# ELC0102_-_Switch_Interface.net
KiCad netlist of a schematic drawn in Altium Designer
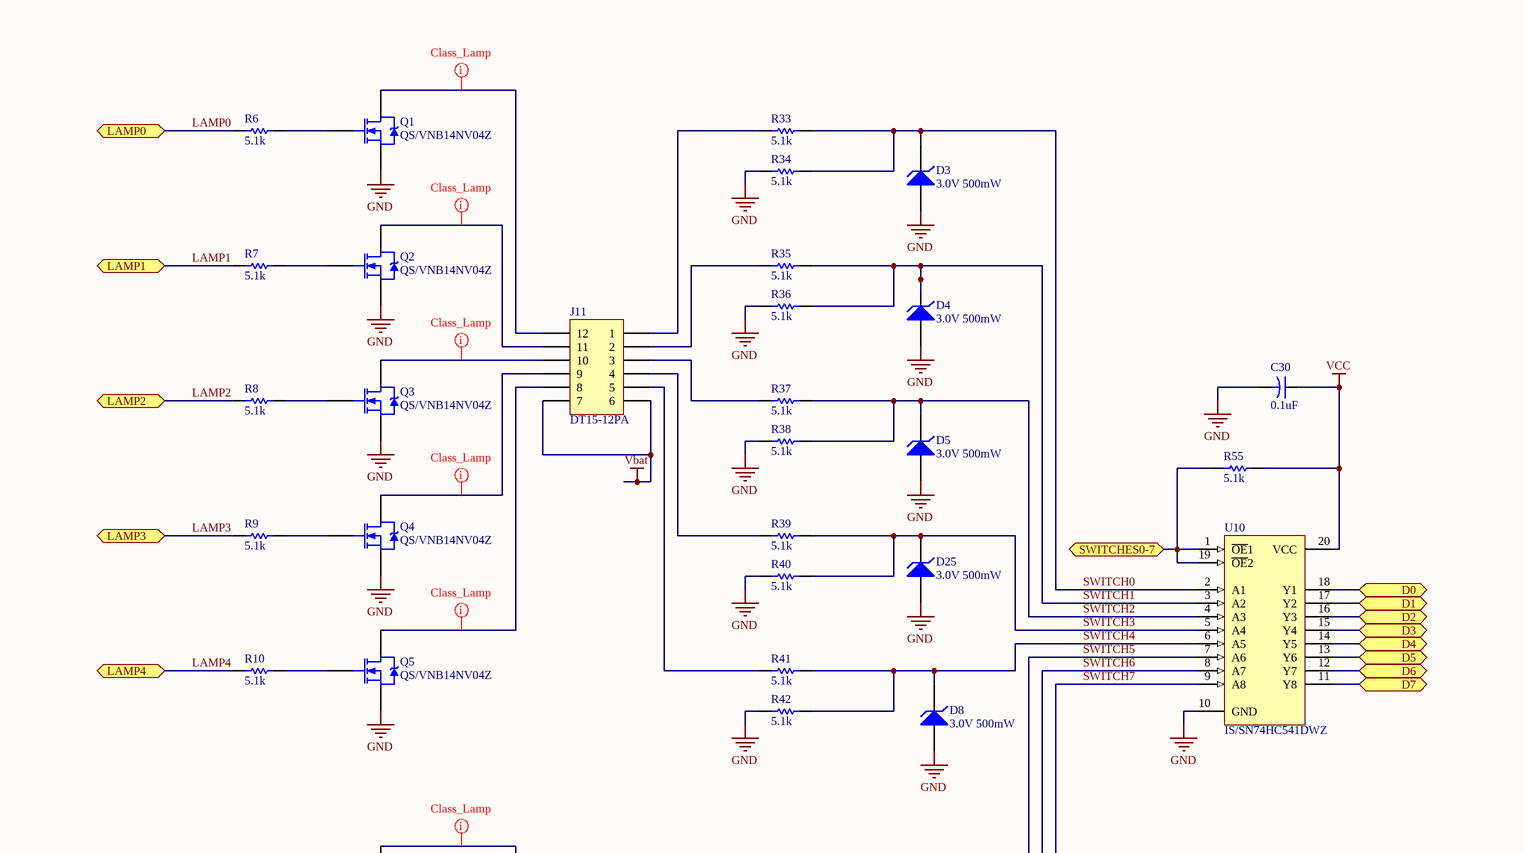
[diagram p0: ELC0102 - Switch Interface.SchDoc, top left]
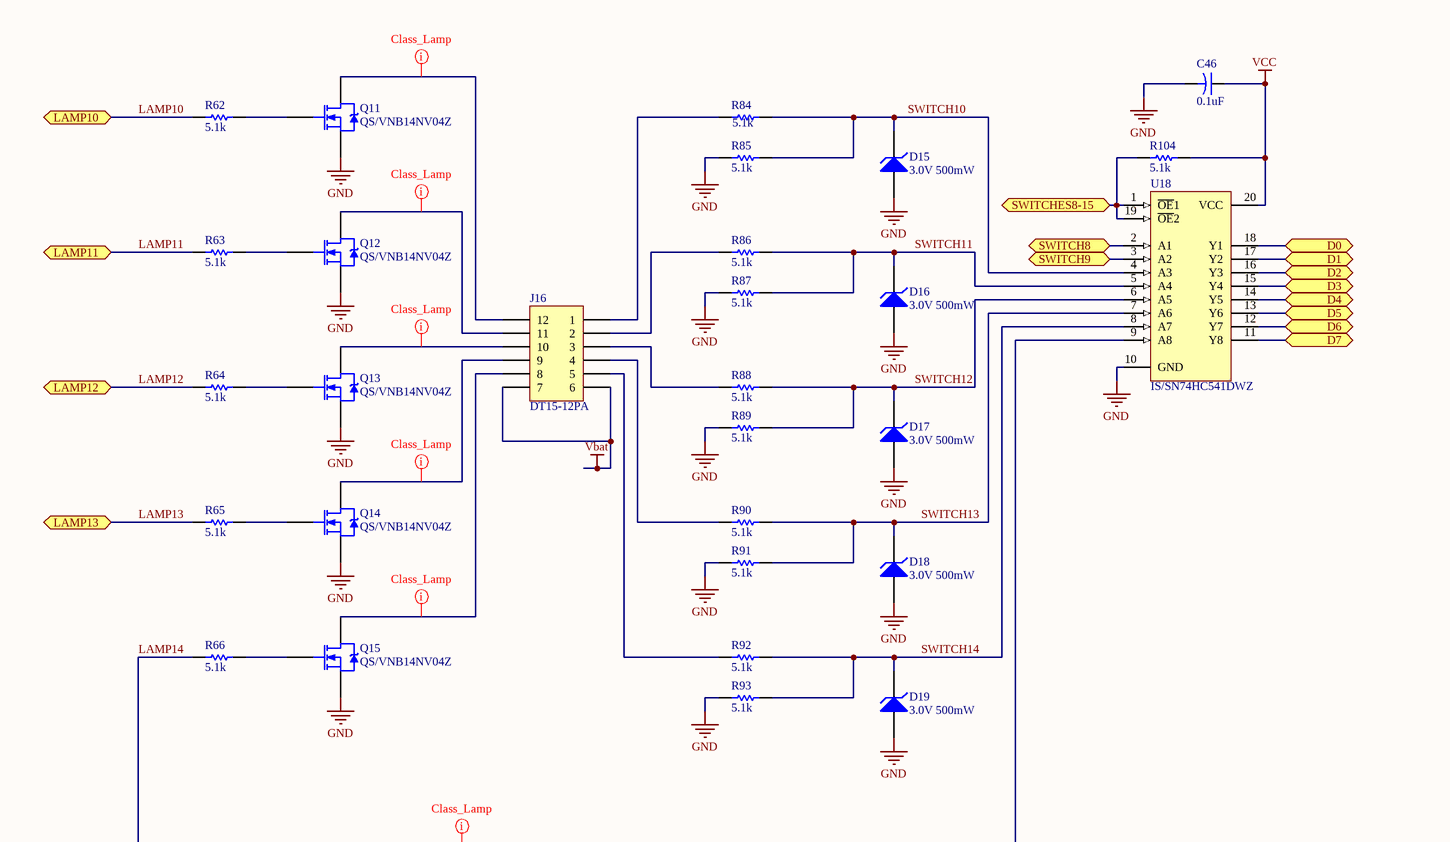
[diagram p1: ELC0102 - Switch Interface.SchDoc, top right]
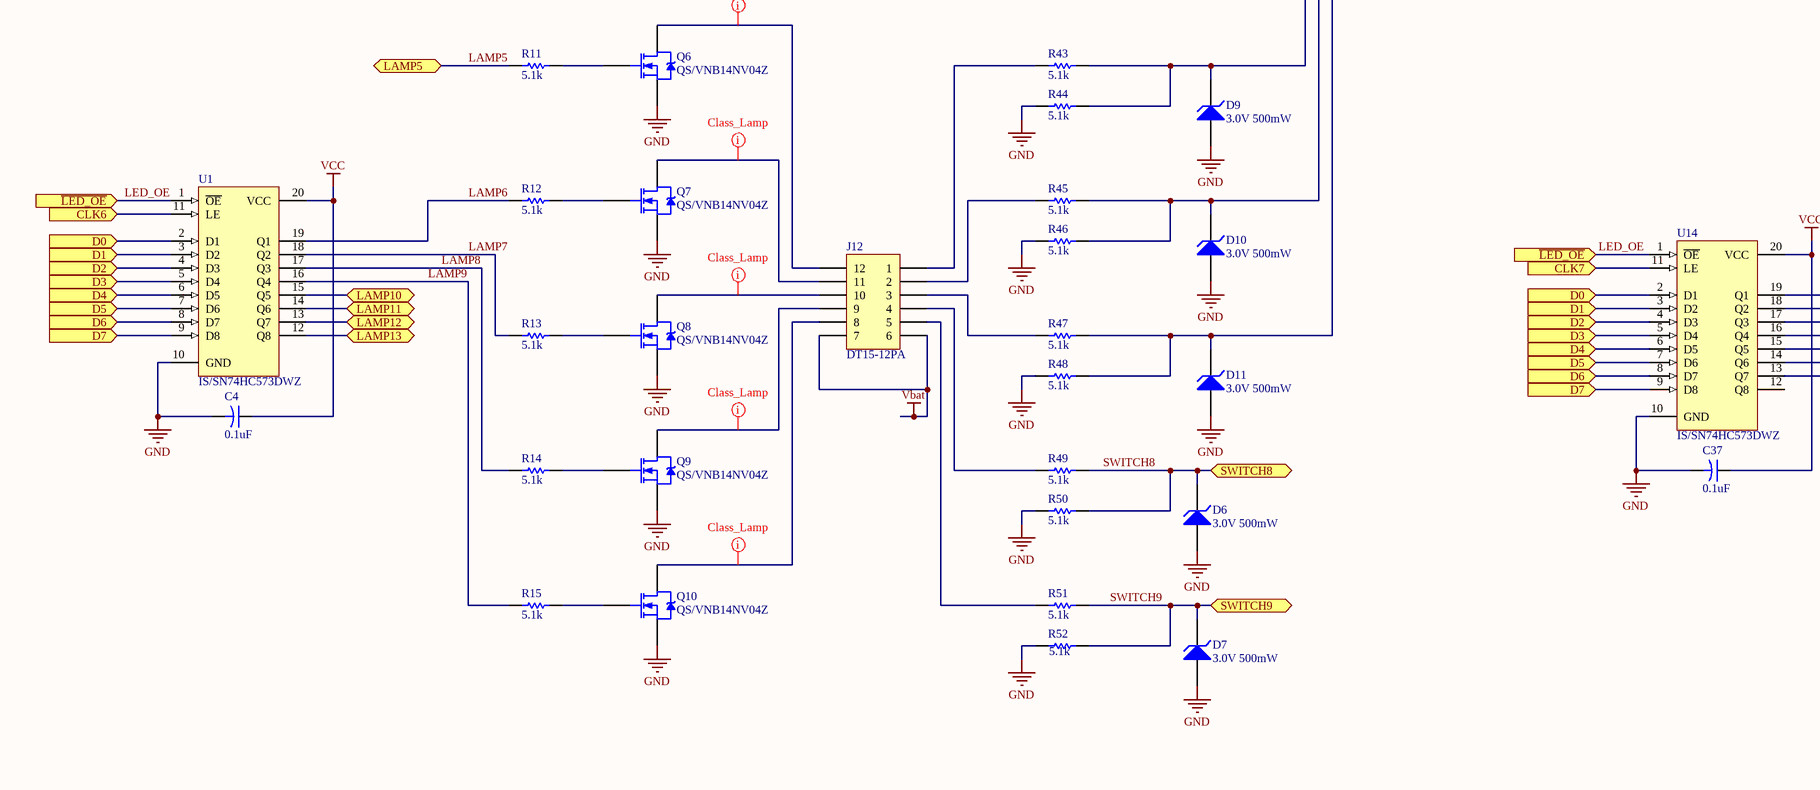
[diagram p2: ELC0102 - Switch Interface.SchDoc, bottom left]
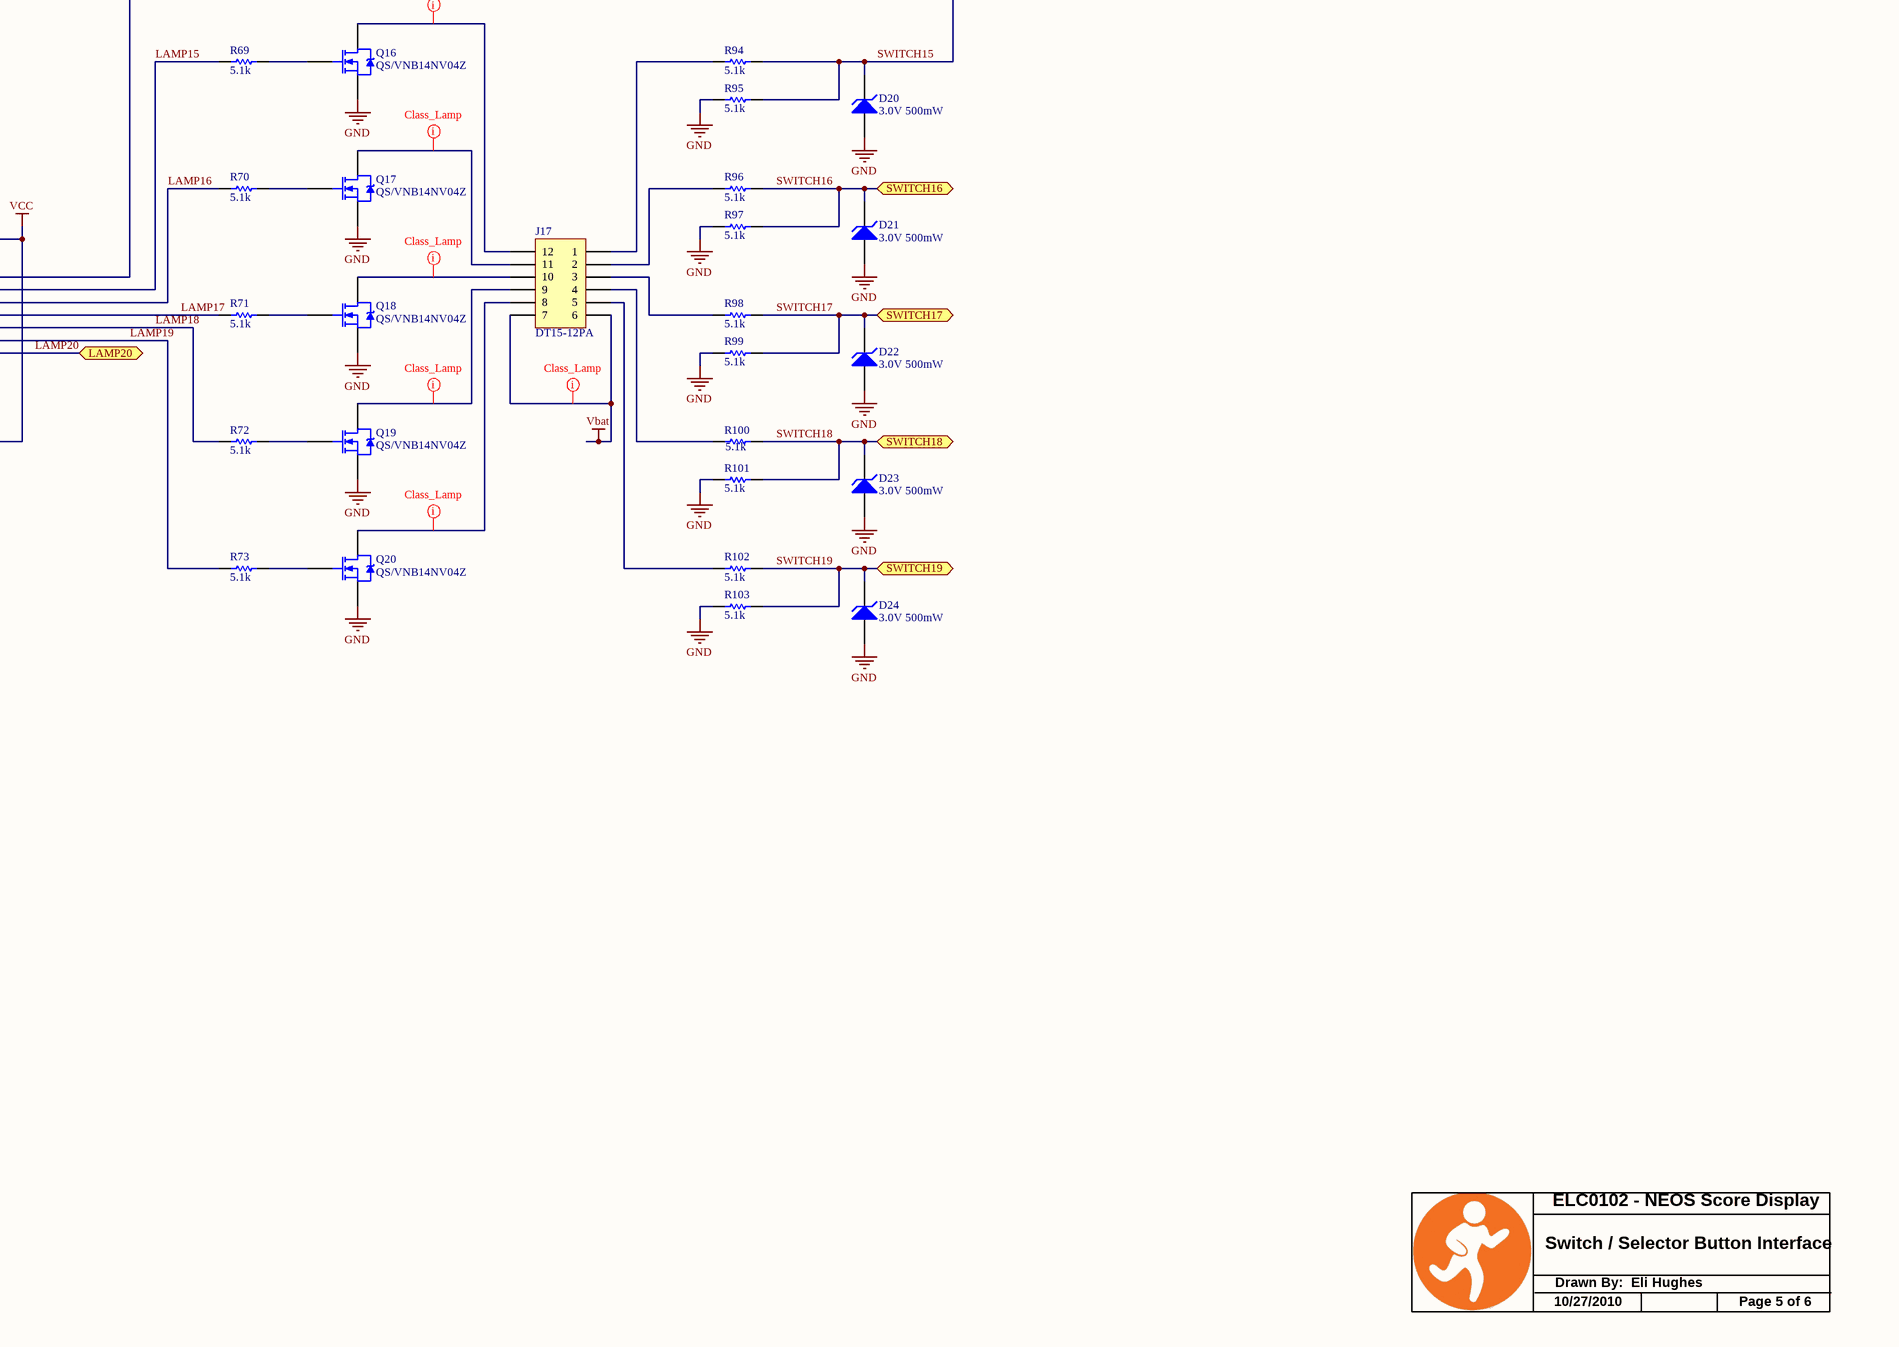
[diagram p3: ELC0102 - Switch Interface.SchDoc, bottom right]

(export (version "E")
  (design (tool "Eeschema 10.0.6"))
  (components
    (comp (ref "C4")
      (value "0.1uF")
      (footprint "C0805")
      (description "CAP .10UF 50V CERAMIC X7R 0805")
      (fields
        (field (name "MANUFACTURER") "Kemet")
        (field (name "MANUFACTURER PART NUMBER") "C0805C104K5RACTU")
        (field (name "SOURCE") "Digikey")
      )
      (libsource (lib "ELC102 - Scoreboard") (part "CS/C0805C104K5RACK"))
    )
    (comp (ref "C30")
      (value "0.1uF")
      (footprint "C0805")
      (description "CAP .10UF 50V CERAMIC X7R 0805")
      (fields
        (field (name "MANUFACTURER") "Kemet")
        (field (name "MANUFACTURER PART NUMBER") "C0805C104K5RACTU")
        (field (name "SOURCE") "Digikey")
      )
      (libsource (lib "ELC102 - Scoreboard") (part "CS/C0805C104K5RACK"))
    )
    (comp (ref "C37")
      (value "0.1uF")
      (footprint "C0805")
      (description "CAP .10UF 50V CERAMIC X7R 0805")
      (fields
        (field (name "MANUFACTURER") "Kemet")
        (field (name "MANUFACTURER PART NUMBER") "C0805C104K5RACTU")
        (field (name "SOURCE") "Digikey")
      )
      (libsource (lib "ELC102 - Scoreboard") (part "CS/C0805C104K5RACK"))
    )
    (comp (ref "C46")
      (value "0.1uF")
      (footprint "C0805")
      (description "CAP .10UF 50V CERAMIC X7R 0805")
      (fields
        (field (name "MANUFACTURER") "Kemet")
        (field (name "MANUFACTURER PART NUMBER") "C0805C104K5RACTU")
        (field (name "SOURCE") "Digikey")
      )
      (libsource (lib "ELC102 - Scoreboard") (part "CS/C0805C104K5RACK"))
    )
    (comp (ref "D3")
      (value "3.0V 500mW")
      (footprint "SOD123")
      (description "Zener 3.0V SOD-123")
      (fields
        (field (name "MANUFACTURER") "ON Semiconductor")
        (field (name "MANUFACTURER PART NUMBER") "MMSZ5225BT1G")
        (field (name "SOURCE") "Digikey")
      )
      (libsource (lib "ScoreBoard") (part "DS/MMSZ5225BT1Z"))
    )
    (comp (ref "D4")
      (value "3.0V 500mW")
      (footprint "SOD123")
      (description "Zener 3.0V SOD-123")
      (fields
        (field (name "MANUFACTURER") "ON Semiconductor")
        (field (name "MANUFACTURER PART NUMBER") "MMSZ5225BT1G")
        (field (name "SOURCE") "Digikey")
      )
      (libsource (lib "ScoreBoard") (part "DS/MMSZ5225BT1Z"))
    )
    (comp (ref "D5")
      (value "3.0V 500mW")
      (footprint "SOD123")
      (description "Zener 3.0V SOD-123")
      (fields
        (field (name "MANUFACTURER") "ON Semiconductor")
        (field (name "MANUFACTURER PART NUMBER") "MMSZ5225BT1G")
        (field (name "SOURCE") "Digikey")
      )
      (libsource (lib "ScoreBoard") (part "DS/MMSZ5225BT1Z"))
    )
    (comp (ref "D6")
      (value "3.0V 500mW")
      (footprint "SOD123")
      (description "Zener 3.0V SOD-123")
      (fields
        (field (name "MANUFACTURER") "ON Semiconductor")
        (field (name "MANUFACTURER PART NUMBER") "MMSZ5225BT1G")
        (field (name "SOURCE") "Digikey")
      )
      (libsource (lib "ScoreBoard") (part "DS/MMSZ5225BT1Z"))
    )
    (comp (ref "D7")
      (value "3.0V 500mW")
      (footprint "SOD123")
      (description "Zener 3.0V SOD-123")
      (fields
        (field (name "MANUFACTURER") "ON Semiconductor")
        (field (name "MANUFACTURER PART NUMBER") "MMSZ5225BT1G")
        (field (name "SOURCE") "Digikey")
      )
      (libsource (lib "ScoreBoard") (part "DS/MMSZ5225BT1Z"))
    )
    (comp (ref "D8")
      (value "3.0V 500mW")
      (footprint "SOD123")
      (description "Zener 3.0V SOD-123")
      (fields
        (field (name "MANUFACTURER") "ON Semiconductor")
        (field (name "MANUFACTURER PART NUMBER") "MMSZ5225BT1G")
        (field (name "SOURCE") "Digikey")
      )
      (libsource (lib "ScoreBoard") (part "DS/MMSZ5225BT1Z"))
    )
    (comp (ref "D9")
      (value "3.0V 500mW")
      (footprint "SOD123")
      (description "Zener 3.0V SOD-123")
      (fields
        (field (name "MANUFACTURER") "ON Semiconductor")
        (field (name "MANUFACTURER PART NUMBER") "MMSZ5225BT1G")
        (field (name "SOURCE") "Digikey")
      )
      (libsource (lib "ScoreBoard") (part "DS/MMSZ5225BT1Z"))
    )
    (comp (ref "D10")
      (value "3.0V 500mW")
      (footprint "SOD123")
      (description "Zener 3.0V SOD-123")
      (fields
        (field (name "MANUFACTURER") "ON Semiconductor")
        (field (name "MANUFACTURER PART NUMBER") "MMSZ5225BT1G")
        (field (name "SOURCE") "Digikey")
      )
      (libsource (lib "ScoreBoard") (part "DS/MMSZ5225BT1Z"))
    )
    (comp (ref "D11")
      (value "3.0V 500mW")
      (footprint "SOD123")
      (description "Zener 3.0V SOD-123")
      (fields
        (field (name "MANUFACTURER") "ON Semiconductor")
        (field (name "MANUFACTURER PART NUMBER") "MMSZ5225BT1G")
        (field (name "SOURCE") "Digikey")
      )
      (libsource (lib "ScoreBoard") (part "DS/MMSZ5225BT1Z"))
    )
    (comp (ref "D15")
      (value "3.0V 500mW")
      (footprint "SOD123")
      (description "Zener 3.0V SOD-123")
      (fields
        (field (name "MANUFACTURER") "ON Semiconductor")
        (field (name "MANUFACTURER PART NUMBER") "MMSZ5225BT1G")
        (field (name "SOURCE") "Digikey")
      )
      (libsource (lib "ScoreBoard") (part "DS/MMSZ5225BT1Z"))
    )
    (comp (ref "D16")
      (value "3.0V 500mW")
      (footprint "SOD123")
      (description "Zener 3.0V SOD-123")
      (fields
        (field (name "MANUFACTURER") "ON Semiconductor")
        (field (name "MANUFACTURER PART NUMBER") "MMSZ5225BT1G")
        (field (name "SOURCE") "Digikey")
      )
      (libsource (lib "ScoreBoard") (part "DS/MMSZ5225BT1Z"))
    )
    (comp (ref "D17")
      (value "3.0V 500mW")
      (footprint "SOD123")
      (description "Zener 3.0V SOD-123")
      (fields
        (field (name "MANUFACTURER") "ON Semiconductor")
        (field (name "MANUFACTURER PART NUMBER") "MMSZ5225BT1G")
        (field (name "SOURCE") "Digikey")
      )
      (libsource (lib "ScoreBoard") (part "DS/MMSZ5225BT1Z"))
    )
    (comp (ref "D18")
      (value "3.0V 500mW")
      (footprint "SOD123")
      (description "Zener 3.0V SOD-123")
      (fields
        (field (name "MANUFACTURER") "ON Semiconductor")
        (field (name "MANUFACTURER PART NUMBER") "MMSZ5225BT1G")
        (field (name "SOURCE") "Digikey")
      )
      (libsource (lib "ScoreBoard") (part "DS/MMSZ5225BT1Z"))
    )
    (comp (ref "D19")
      (value "3.0V 500mW")
      (footprint "SOD123")
      (description "Zener 3.0V SOD-123")
      (fields
        (field (name "MANUFACTURER") "ON Semiconductor")
        (field (name "MANUFACTURER PART NUMBER") "MMSZ5225BT1G")
        (field (name "SOURCE") "Digikey")
      )
      (libsource (lib "ScoreBoard") (part "DS/MMSZ5225BT1Z"))
    )
    (comp (ref "D20")
      (value "3.0V 500mW")
      (footprint "SOD123")
      (description "Zener 3.0V SOD-123")
      (fields
        (field (name "MANUFACTURER") "ON Semiconductor")
        (field (name "MANUFACTURER PART NUMBER") "MMSZ5225BT1G")
        (field (name "SOURCE") "Digikey")
      )
      (libsource (lib "ScoreBoard") (part "DS/MMSZ5225BT1Z"))
    )
    (comp (ref "D21")
      (value "3.0V 500mW")
      (footprint "SOD123")
      (description "Zener 3.0V SOD-123")
      (fields
        (field (name "MANUFACTURER") "ON Semiconductor")
        (field (name "MANUFACTURER PART NUMBER") "MMSZ5225BT1G")
        (field (name "SOURCE") "Digikey")
      )
      (libsource (lib "ScoreBoard") (part "DS/MMSZ5225BT1Z"))
    )
    (comp (ref "D22")
      (value "3.0V 500mW")
      (footprint "SOD123")
      (description "Zener 3.0V SOD-123")
      (fields
        (field (name "MANUFACTURER") "ON Semiconductor")
        (field (name "MANUFACTURER PART NUMBER") "MMSZ5225BT1G")
        (field (name "SOURCE") "Digikey")
      )
      (libsource (lib "ScoreBoard") (part "DS/MMSZ5225BT1Z"))
    )
    (comp (ref "D23")
      (value "3.0V 500mW")
      (footprint "SOD123")
      (description "Zener 3.0V SOD-123")
      (fields
        (field (name "MANUFACTURER") "ON Semiconductor")
        (field (name "MANUFACTURER PART NUMBER") "MMSZ5225BT1G")
        (field (name "SOURCE") "Digikey")
      )
      (libsource (lib "ScoreBoard") (part "DS/MMSZ5225BT1Z"))
    )
    (comp (ref "D24")
      (value "3.0V 500mW")
      (footprint "SOD123")
      (description "Zener 3.0V SOD-123")
      (fields
        (field (name "MANUFACTURER") "ON Semiconductor")
        (field (name "MANUFACTURER PART NUMBER") "MMSZ5225BT1G")
        (field (name "SOURCE") "Digikey")
      )
      (libsource (lib "ScoreBoard") (part "DS/MMSZ5225BT1Z"))
    )
    (comp (ref "D25")
      (value "3.0V 500mW")
      (footprint "SOD123")
      (description "Zener 3.0V SOD-123")
      (fields
        (field (name "MANUFACTURER") "ON Semiconductor")
        (field (name "MANUFACTURER PART NUMBER") "MMSZ5225BT1G")
        (field (name "SOURCE") "Digikey")
      )
      (libsource (lib "ScoreBoard") (part "DS/MMSZ5225BT1Z"))
    )
    (comp (ref "J11")
      (value "DT15-12PA")
      (footprint "JDT1512PA00Z")
      (description "Deutsch 12P Sealed PCB connector")
      (fields (field (name "MANUFACTURER") "Deutsch"))
      (libsource (lib "ScoreBoard") (part "JDT1512PA00Z"))
    )
    (comp (ref "J12")
      (value "DT15-12PA")
      (footprint "JDT1512PA00Z")
      (description "Deutsch 12P Sealed PCB connector")
      (fields (field (name "MANUFACTURER") "Deutsch"))
      (libsource (lib "ScoreBoard") (part "JDT1512PA00Z"))
    )
    (comp (ref "J16")
      (value "DT15-12PA")
      (footprint "JDT1512PA00Z")
      (description "Deutsch 12P Sealed PCB connector")
      (fields (field (name "MANUFACTURER") "Deutsch"))
      (libsource (lib "ScoreBoard") (part "JDT1512PA00Z"))
    )
    (comp (ref "J17")
      (value "DT15-12PA")
      (footprint "JDT1512PA00Z")
      (description "Deutsch 12P Sealed PCB connector")
      (fields (field (name "MANUFACTURER") "Deutsch"))
      (libsource (lib "ScoreBoard") (part "JDT1512PA00Z"))
    )
    (comp (ref "Q1")
      (value "QS/VNB14NV04Z")
      (footprint "D2PAK")
      (description "HEXFET Power MOSFET")
      (fields
        (field (name "MANUFACTURER") "STMicroelectronics")
        (field (name "MANUFACTURER PART NUMBER") "VNB14NV04")
        (field (name "SOURCE") "Digikey")
      )
      (libsource (lib "ScoreBoard") (part "QS/VNB14NV04Z"))
    )
    (comp (ref "Q2")
      (value "QS/VNB14NV04Z")
      (footprint "D2PAK")
      (description "HEXFET Power MOSFET")
      (fields
        (field (name "MANUFACTURER") "STMicroelectronics")
        (field (name "MANUFACTURER PART NUMBER") "VNB14NV04")
        (field (name "SOURCE") "Digikey")
      )
      (libsource (lib "ScoreBoard") (part "QS/VNB14NV04Z"))
    )
    (comp (ref "Q3")
      (value "QS/VNB14NV04Z")
      (footprint "D2PAK")
      (description "HEXFET Power MOSFET")
      (fields
        (field (name "MANUFACTURER") "STMicroelectronics")
        (field (name "MANUFACTURER PART NUMBER") "VNB14NV04")
        (field (name "SOURCE") "Digikey")
      )
      (libsource (lib "ScoreBoard") (part "QS/VNB14NV04Z"))
    )
    (comp (ref "Q4")
      (value "QS/VNB14NV04Z")
      (footprint "D2PAK")
      (description "HEXFET Power MOSFET")
      (fields
        (field (name "MANUFACTURER") "STMicroelectronics")
        (field (name "MANUFACTURER PART NUMBER") "VNB14NV04")
        (field (name "SOURCE") "Digikey")
      )
      (libsource (lib "ScoreBoard") (part "QS/VNB14NV04Z"))
    )
    (comp (ref "Q5")
      (value "QS/VNB14NV04Z")
      (footprint "D2PAK")
      (description "HEXFET Power MOSFET")
      (fields
        (field (name "MANUFACTURER") "STMicroelectronics")
        (field (name "MANUFACTURER PART NUMBER") "VNB14NV04")
        (field (name "SOURCE") "Digikey")
      )
      (libsource (lib "ScoreBoard") (part "QS/VNB14NV04Z"))
    )
    (comp (ref "Q6")
      (value "QS/VNB14NV04Z")
      (footprint "D2PAK")
      (description "HEXFET Power MOSFET")
      (fields
        (field (name "MANUFACTURER") "STMicroelectronics")
        (field (name "MANUFACTURER PART NUMBER") "VNB14NV04")
        (field (name "SOURCE") "Digikey")
      )
      (libsource (lib "ScoreBoard") (part "QS/VNB14NV04Z"))
    )
    (comp (ref "Q7")
      (value "QS/VNB14NV04Z")
      (footprint "D2PAK")
      (description "HEXFET Power MOSFET")
      (fields
        (field (name "MANUFACTURER") "STMicroelectronics")
        (field (name "MANUFACTURER PART NUMBER") "VNB14NV04")
        (field (name "SOURCE") "Digikey")
      )
      (libsource (lib "ScoreBoard") (part "QS/VNB14NV04Z"))
    )
    (comp (ref "Q8")
      (value "QS/VNB14NV04Z")
      (footprint "D2PAK")
      (description "HEXFET Power MOSFET")
      (fields
        (field (name "MANUFACTURER") "STMicroelectronics")
        (field (name "MANUFACTURER PART NUMBER") "VNB14NV04")
        (field (name "SOURCE") "Digikey")
      )
      (libsource (lib "ScoreBoard") (part "QS/VNB14NV04Z"))
    )
    (comp (ref "Q9")
      (value "QS/VNB14NV04Z")
      (footprint "D2PAK")
      (description "HEXFET Power MOSFET")
      (fields
        (field (name "MANUFACTURER") "STMicroelectronics")
        (field (name "MANUFACTURER PART NUMBER") "VNB14NV04")
        (field (name "SOURCE") "Digikey")
      )
      (libsource (lib "ScoreBoard") (part "QS/VNB14NV04Z"))
    )
    (comp (ref "Q10")
      (value "QS/VNB14NV04Z")
      (footprint "D2PAK")
      (description "HEXFET Power MOSFET")
      (fields
        (field (name "MANUFACTURER") "STMicroelectronics")
        (field (name "MANUFACTURER PART NUMBER") "VNB14NV04")
        (field (name "SOURCE") "Digikey")
      )
      (libsource (lib "ScoreBoard") (part "QS/VNB14NV04Z"))
    )
    (comp (ref "Q11")
      (value "QS/VNB14NV04Z")
      (footprint "D2PAK")
      (description "HEXFET Power MOSFET")
      (fields
        (field (name "MANUFACTURER") "STMicroelectronics")
        (field (name "MANUFACTURER PART NUMBER") "VNB14NV04")
        (field (name "SOURCE") "Digikey")
      )
      (libsource (lib "ScoreBoard") (part "QS/VNB14NV04Z"))
    )
    (comp (ref "Q12")
      (value "QS/VNB14NV04Z")
      (footprint "D2PAK")
      (description "HEXFET Power MOSFET")
      (fields
        (field (name "MANUFACTURER") "STMicroelectronics")
        (field (name "MANUFACTURER PART NUMBER") "VNB14NV04")
        (field (name "SOURCE") "Digikey")
      )
      (libsource (lib "ScoreBoard") (part "QS/VNB14NV04Z"))
    )
    (comp (ref "Q13")
      (value "QS/VNB14NV04Z")
      (footprint "D2PAK")
      (description "HEXFET Power MOSFET")
      (fields
        (field (name "MANUFACTURER") "STMicroelectronics")
        (field (name "MANUFACTURER PART NUMBER") "VNB14NV04")
        (field (name "SOURCE") "Digikey")
      )
      (libsource (lib "ScoreBoard") (part "QS/VNB14NV04Z"))
    )
    (comp (ref "Q14")
      (value "QS/VNB14NV04Z")
      (footprint "D2PAK")
      (description "HEXFET Power MOSFET")
      (fields
        (field (name "MANUFACTURER") "STMicroelectronics")
        (field (name "MANUFACTURER PART NUMBER") "VNB14NV04")
        (field (name "SOURCE") "Digikey")
      )
      (libsource (lib "ScoreBoard") (part "QS/VNB14NV04Z"))
    )
    (comp (ref "Q15")
      (value "QS/VNB14NV04Z")
      (footprint "D2PAK")
      (description "HEXFET Power MOSFET")
      (fields
        (field (name "MANUFACTURER") "STMicroelectronics")
        (field (name "MANUFACTURER PART NUMBER") "VNB14NV04")
        (field (name "SOURCE") "Digikey")
      )
      (libsource (lib "ScoreBoard") (part "QS/VNB14NV04Z"))
    )
    (comp (ref "Q16")
      (value "QS/VNB14NV04Z")
      (footprint "D2PAK")
      (description "HEXFET Power MOSFET")
      (fields
        (field (name "MANUFACTURER") "STMicroelectronics")
        (field (name "MANUFACTURER PART NUMBER") "VNB14NV04")
        (field (name "SOURCE") "Digikey")
      )
      (libsource (lib "ScoreBoard") (part "QS/VNB14NV04Z"))
    )
    (comp (ref "Q17")
      (value "QS/VNB14NV04Z")
      (footprint "D2PAK")
      (description "HEXFET Power MOSFET")
      (fields
        (field (name "MANUFACTURER") "STMicroelectronics")
        (field (name "MANUFACTURER PART NUMBER") "VNB14NV04")
        (field (name "SOURCE") "Digikey")
      )
      (libsource (lib "ScoreBoard") (part "QS/VNB14NV04Z"))
    )
    (comp (ref "Q18")
      (value "QS/VNB14NV04Z")
      (footprint "D2PAK")
      (description "HEXFET Power MOSFET")
      (fields
        (field (name "MANUFACTURER") "STMicroelectronics")
        (field (name "MANUFACTURER PART NUMBER") "VNB14NV04")
        (field (name "SOURCE") "Digikey")
      )
      (libsource (lib "ScoreBoard") (part "QS/VNB14NV04Z"))
    )
    (comp (ref "Q19")
      (value "QS/VNB14NV04Z")
      (footprint "D2PAK")
      (description "HEXFET Power MOSFET")
      (fields
        (field (name "MANUFACTURER") "STMicroelectronics")
        (field (name "MANUFACTURER PART NUMBER") "VNB14NV04")
        (field (name "SOURCE") "Digikey")
      )
      (libsource (lib "ScoreBoard") (part "QS/VNB14NV04Z"))
    )
    (comp (ref "Q20")
      (value "QS/VNB14NV04Z")
      (footprint "D2PAK")
      (description "HEXFET Power MOSFET")
      (fields
        (field (name "MANUFACTURER") "STMicroelectronics")
        (field (name "MANUFACTURER PART NUMBER") "VNB14NV04")
        (field (name "SOURCE") "Digikey")
      )
      (libsource (lib "ScoreBoard") (part "QS/VNB14NV04Z"))
    )
    (comp (ref "R6")
      (value "5.1k")
      (footprint "R0805")
      (description "RES 5.10K OHM 1/8W 1% 0805 SMD")
      (fields
        (field (name "MANUFACTURER") "Panasonic - ECG")
        (field (name "MANUFACTURER PART NUMBER") "ERJ-6ENF5101V")
      )
      (libsource (lib "eRCL") (part "ERJ-6ENF5101V"))
    )
    (comp (ref "R7")
      (value "5.1k")
      (footprint "R0805")
      (description "RES 5.10K OHM 1/8W 1% 0805 SMD")
      (fields
        (field (name "MANUFACTURER") "Panasonic - ECG")
        (field (name "MANUFACTURER PART NUMBER") "ERJ-6ENF5101V")
      )
      (libsource (lib "eRCL") (part "ERJ-6ENF5101V"))
    )
    (comp (ref "R8")
      (value "5.1k")
      (footprint "R0805")
      (description "RES 5.10K OHM 1/8W 1% 0805 SMD")
      (fields
        (field (name "MANUFACTURER") "Panasonic - ECG")
        (field (name "MANUFACTURER PART NUMBER") "ERJ-6ENF5101V")
      )
      (libsource (lib "eRCL") (part "ERJ-6ENF5101V"))
    )
    (comp (ref "R9")
      (value "5.1k")
      (footprint "R0805")
      (description "RES 5.10K OHM 1/8W 1% 0805 SMD")
      (fields
        (field (name "MANUFACTURER") "Panasonic - ECG")
        (field (name "MANUFACTURER PART NUMBER") "ERJ-6ENF5101V")
      )
      (libsource (lib "eRCL") (part "ERJ-6ENF5101V"))
    )
    (comp (ref "R10")
      (value "5.1k")
      (footprint "R0805")
      (description "RES 5.10K OHM 1/8W 1% 0805 SMD")
      (fields
        (field (name "MANUFACTURER") "Panasonic - ECG")
        (field (name "MANUFACTURER PART NUMBER") "ERJ-6ENF5101V")
      )
      (libsource (lib "eRCL") (part "ERJ-6ENF5101V"))
    )
    (comp (ref "R11")
      (value "5.1k")
      (footprint "R0805")
      (description "RES 5.10K OHM 1/8W 1% 0805 SMD")
      (fields
        (field (name "MANUFACTURER") "Panasonic - ECG")
        (field (name "MANUFACTURER PART NUMBER") "ERJ-6ENF5101V")
      )
      (libsource (lib "eRCL") (part "ERJ-6ENF5101V"))
    )
    (comp (ref "R12")
      (value "5.1k")
      (footprint "R0805")
      (description "RES 5.10K OHM 1/8W 1% 0805 SMD")
      (fields
        (field (name "MANUFACTURER") "Panasonic - ECG")
        (field (name "MANUFACTURER PART NUMBER") "ERJ-6ENF5101V")
      )
      (libsource (lib "eRCL") (part "ERJ-6ENF5101V"))
    )
    (comp (ref "R13")
      (value "5.1k")
      (footprint "R0805")
      (description "RES 5.10K OHM 1/8W 1% 0805 SMD")
      (fields
        (field (name "MANUFACTURER") "Panasonic - ECG")
        (field (name "MANUFACTURER PART NUMBER") "ERJ-6ENF5101V")
      )
      (libsource (lib "eRCL") (part "ERJ-6ENF5101V"))
    )
    (comp (ref "R14")
      (value "5.1k")
      (footprint "R0805")
      (description "RES 5.10K OHM 1/8W 1% 0805 SMD")
      (fields
        (field (name "MANUFACTURER") "Panasonic - ECG")
        (field (name "MANUFACTURER PART NUMBER") "ERJ-6ENF5101V")
      )
      (libsource (lib "eRCL") (part "ERJ-6ENF5101V"))
    )
    (comp (ref "R15")
      (value "5.1k")
      (footprint "R0805")
      (description "RES 5.10K OHM 1/8W 1% 0805 SMD")
      (fields
        (field (name "MANUFACTURER") "Panasonic - ECG")
        (field (name "MANUFACTURER PART NUMBER") "ERJ-6ENF5101V")
      )
      (libsource (lib "eRCL") (part "ERJ-6ENF5101V"))
    )
    (comp (ref "R33")
      (value "5.1k")
      (footprint "R0805")
      (description "RES 5.10K OHM 1/8W 1% 0805 SMD")
      (fields
        (field (name "MANUFACTURER") "Panasonic - ECG")
        (field (name "MANUFACTURER PART NUMBER") "ERJ-6ENF5101V")
      )
      (libsource (lib "eRCL") (part "ERJ-6ENF5101V"))
    )
    (comp (ref "R34")
      (value "5.1k")
      (footprint "R0805")
      (description "RES 5.10K OHM 1/8W 1% 0805 SMD")
      (fields
        (field (name "MANUFACTURER") "Panasonic - ECG")
        (field (name "MANUFACTURER PART NUMBER") "ERJ-6ENF5101V")
      )
      (libsource (lib "eRCL") (part "ERJ-6ENF5101V"))
    )
    (comp (ref "R35")
      (value "5.1k")
      (footprint "R0805")
      (description "RES 5.10K OHM 1/8W 1% 0805 SMD")
      (fields
        (field (name "MANUFACTURER") "Panasonic - ECG")
        (field (name "MANUFACTURER PART NUMBER") "ERJ-6ENF5101V")
      )
      (libsource (lib "eRCL") (part "ERJ-6ENF5101V"))
    )
    (comp (ref "R36")
      (value "5.1k")
      (footprint "R0805")
      (description "RES 5.10K OHM 1/8W 1% 0805 SMD")
      (fields
        (field (name "MANUFACTURER") "Panasonic - ECG")
        (field (name "MANUFACTURER PART NUMBER") "ERJ-6ENF5101V")
      )
      (libsource (lib "eRCL") (part "ERJ-6ENF5101V"))
    )
    (comp (ref "R37")
      (value "5.1k")
      (footprint "R0805")
      (description "RES 5.10K OHM 1/8W 1% 0805 SMD")
      (fields
        (field (name "MANUFACTURER") "Panasonic - ECG")
        (field (name "MANUFACTURER PART NUMBER") "ERJ-6ENF5101V")
      )
      (libsource (lib "eRCL") (part "ERJ-6ENF5101V"))
    )
    (comp (ref "R38")
      (value "5.1k")
      (footprint "R0805")
      (description "RES 5.10K OHM 1/8W 1% 0805 SMD")
      (fields
        (field (name "MANUFACTURER") "Panasonic - ECG")
        (field (name "MANUFACTURER PART NUMBER") "ERJ-6ENF5101V")
      )
      (libsource (lib "eRCL") (part "ERJ-6ENF5101V"))
    )
    (comp (ref "R39")
      (value "5.1k")
      (footprint "R0805")
      (description "RES 5.10K OHM 1/8W 1% 0805 SMD")
      (fields
        (field (name "MANUFACTURER") "Panasonic - ECG")
        (field (name "MANUFACTURER PART NUMBER") "ERJ-6ENF5101V")
      )
      (libsource (lib "eRCL") (part "ERJ-6ENF5101V"))
    )
    (comp (ref "R40")
      (value "5.1k")
      (footprint "R0805")
      (description "RES 5.10K OHM 1/8W 1% 0805 SMD")
      (fields
        (field (name "MANUFACTURER") "Panasonic - ECG")
        (field (name "MANUFACTURER PART NUMBER") "ERJ-6ENF5101V")
      )
      (libsource (lib "eRCL") (part "ERJ-6ENF5101V"))
    )
    (comp (ref "R41")
      (value "5.1k")
      (footprint "R0805")
      (description "RES 5.10K OHM 1/8W 1% 0805 SMD")
      (fields
        (field (name "MANUFACTURER") "Panasonic - ECG")
        (field (name "MANUFACTURER PART NUMBER") "ERJ-6ENF5101V")
      )
      (libsource (lib "eRCL") (part "ERJ-6ENF5101V"))
    )
    (comp (ref "R42")
      (value "5.1k")
      (footprint "R0805")
      (description "RES 5.10K OHM 1/8W 1% 0805 SMD")
      (fields
        (field (name "MANUFACTURER") "Panasonic - ECG")
        (field (name "MANUFACTURER PART NUMBER") "ERJ-6ENF5101V")
      )
      (libsource (lib "eRCL") (part "ERJ-6ENF5101V"))
    )
    (comp (ref "R43")
      (value "5.1k")
      (footprint "R0805")
      (description "RES 5.10K OHM 1/8W 1% 0805 SMD")
      (fields
        (field (name "MANUFACTURER") "Panasonic - ECG")
        (field (name "MANUFACTURER PART NUMBER") "ERJ-6ENF5101V")
      )
      (libsource (lib "eRCL") (part "ERJ-6ENF5101V"))
    )
    (comp (ref "R44")
      (value "5.1k")
      (footprint "R0805")
      (description "RES 5.10K OHM 1/8W 1% 0805 SMD")
      (fields
        (field (name "MANUFACTURER") "Panasonic - ECG")
        (field (name "MANUFACTURER PART NUMBER") "ERJ-6ENF5101V")
      )
      (libsource (lib "eRCL") (part "ERJ-6ENF5101V"))
    )
    (comp (ref "R45")
      (value "5.1k")
      (footprint "R0805")
      (description "RES 5.10K OHM 1/8W 1% 0805 SMD")
      (fields
        (field (name "MANUFACTURER") "Panasonic - ECG")
        (field (name "MANUFACTURER PART NUMBER") "ERJ-6ENF5101V")
      )
      (libsource (lib "eRCL") (part "ERJ-6ENF5101V"))
    )
    (comp (ref "R46")
      (value "5.1k")
      (footprint "R0805")
      (description "RES 5.10K OHM 1/8W 1% 0805 SMD")
      (fields
        (field (name "MANUFACTURER") "Panasonic - ECG")
        (field (name "MANUFACTURER PART NUMBER") "ERJ-6ENF5101V")
      )
      (libsource (lib "eRCL") (part "ERJ-6ENF5101V"))
    )
    (comp (ref "R47")
      (value "5.1k")
      (footprint "R0805")
      (description "RES 5.10K OHM 1/8W 1% 0805 SMD")
      (fields
        (field (name "MANUFACTURER") "Panasonic - ECG")
        (field (name "MANUFACTURER PART NUMBER") "ERJ-6ENF5101V")
      )
      (libsource (lib "eRCL") (part "ERJ-6ENF5101V"))
    )
    (comp (ref "R48")
      (value "5.1k")
      (footprint "R0805")
      (description "RES 5.10K OHM 1/8W 1% 0805 SMD")
      (fields
        (field (name "MANUFACTURER") "Panasonic - ECG")
        (field (name "MANUFACTURER PART NUMBER") "ERJ-6ENF5101V")
      )
      (libsource (lib "eRCL") (part "ERJ-6ENF5101V"))
    )
    (comp (ref "R49")
      (value "5.1k")
      (footprint "R0805")
      (description "RES 5.10K OHM 1/8W 1% 0805 SMD")
      (fields
        (field (name "MANUFACTURER") "Panasonic - ECG")
        (field (name "MANUFACTURER PART NUMBER") "ERJ-6ENF5101V")
      )
      (libsource (lib "eRCL") (part "ERJ-6ENF5101V"))
    )
    (comp (ref "R50")
      (value "5.1k")
      (footprint "R0805")
      (description "RES 5.10K OHM 1/8W 1% 0805 SMD")
      (fields
        (field (name "MANUFACTURER") "Panasonic - ECG")
        (field (name "MANUFACTURER PART NUMBER") "ERJ-6ENF5101V")
      )
      (libsource (lib "eRCL") (part "ERJ-6ENF5101V"))
    )
    (comp (ref "R51")
      (value "5.1k")
      (footprint "R0805")
      (description "RES 5.10K OHM 1/8W 1% 0805 SMD")
      (fields
        (field (name "MANUFACTURER") "Panasonic - ECG")
        (field (name "MANUFACTURER PART NUMBER") "ERJ-6ENF5101V")
      )
      (libsource (lib "eRCL") (part "ERJ-6ENF5101V"))
    )
    (comp (ref "R52")
      (value "5.1k")
      (footprint "R0805")
      (description "RES 5.10K OHM 1/8W 1% 0805 SMD")
      (fields
        (field (name "MANUFACTURER") "Panasonic - ECG")
        (field (name "MANUFACTURER PART NUMBER") "ERJ-6ENF5101V")
      )
      (libsource (lib "eRCL") (part "ERJ-6ENF5101V"))
    )
    (comp (ref "R55")
      (value "5.1k")
      (footprint "R0805")
      (description "RES 5.10K OHM 1/8W 1% 0805 SMD")
      (fields
        (field (name "MANUFACTURER") "Panasonic - ECG")
        (field (name "MANUFACTURER PART NUMBER") "ERJ-6ENF5101V")
      )
      (libsource (lib "eRCL") (part "ERJ-6ENF5101V"))
    )
    (comp (ref "R62")
      (value "5.1k")
      (footprint "R0805")
      (description "RES 5.10K OHM 1/8W 1% 0805 SMD")
      (fields
        (field (name "MANUFACTURER") "Panasonic - ECG")
        (field (name "MANUFACTURER PART NUMBER") "ERJ-6ENF5101V")
      )
      (libsource (lib "eRCL") (part "ERJ-6ENF5101V"))
    )
    (comp (ref "R63")
      (value "5.1k")
      (footprint "R0805")
      (description "RES 5.10K OHM 1/8W 1% 0805 SMD")
      (fields
        (field (name "MANUFACTURER") "Panasonic - ECG")
        (field (name "MANUFACTURER PART NUMBER") "ERJ-6ENF5101V")
      )
      (libsource (lib "eRCL") (part "ERJ-6ENF5101V"))
    )
    (comp (ref "R64")
      (value "5.1k")
      (footprint "R0805")
      (description "RES 5.10K OHM 1/8W 1% 0805 SMD")
      (fields
        (field (name "MANUFACTURER") "Panasonic - ECG")
        (field (name "MANUFACTURER PART NUMBER") "ERJ-6ENF5101V")
      )
      (libsource (lib "eRCL") (part "ERJ-6ENF5101V"))
    )
    (comp (ref "R65")
      (value "5.1k")
      (footprint "R0805")
      (description "RES 5.10K OHM 1/8W 1% 0805 SMD")
      (fields
        (field (name "MANUFACTURER") "Panasonic - ECG")
        (field (name "MANUFACTURER PART NUMBER") "ERJ-6ENF5101V")
      )
      (libsource (lib "eRCL") (part "ERJ-6ENF5101V"))
    )
    (comp (ref "R66")
      (value "5.1k")
      (footprint "R0805")
      (description "RES 5.10K OHM 1/8W 1% 0805 SMD")
      (fields
        (field (name "MANUFACTURER") "Panasonic - ECG")
        (field (name "MANUFACTURER PART NUMBER") "ERJ-6ENF5101V")
      )
      (libsource (lib "eRCL") (part "ERJ-6ENF5101V"))
    )
    (comp (ref "R69")
      (value "5.1k")
      (footprint "R0805")
      (description "RES 5.10K OHM 1/8W 1% 0805 SMD")
      (fields
        (field (name "MANUFACTURER") "Panasonic - ECG")
        (field (name "MANUFACTURER PART NUMBER") "ERJ-6ENF5101V")
      )
      (libsource (lib "eRCL") (part "ERJ-6ENF5101V"))
    )
    (comp (ref "R70")
      (value "5.1k")
      (footprint "R0805")
      (description "RES 5.10K OHM 1/8W 1% 0805 SMD")
      (fields
        (field (name "MANUFACTURER") "Panasonic - ECG")
        (field (name "MANUFACTURER PART NUMBER") "ERJ-6ENF5101V")
      )
      (libsource (lib "eRCL") (part "ERJ-6ENF5101V"))
    )
    (comp (ref "R71")
      (value "5.1k")
      (footprint "R0805")
      (description "RES 5.10K OHM 1/8W 1% 0805 SMD")
      (fields
        (field (name "MANUFACTURER") "Panasonic - ECG")
        (field (name "MANUFACTURER PART NUMBER") "ERJ-6ENF5101V")
      )
      (libsource (lib "eRCL") (part "ERJ-6ENF5101V"))
    )
    (comp (ref "R72")
      (value "5.1k")
      (footprint "R0805")
      (description "RES 5.10K OHM 1/8W 1% 0805 SMD")
      (fields
        (field (name "MANUFACTURER") "Panasonic - ECG")
        (field (name "MANUFACTURER PART NUMBER") "ERJ-6ENF5101V")
      )
      (libsource (lib "eRCL") (part "ERJ-6ENF5101V"))
    )
    (comp (ref "R73")
      (value "5.1k")
      (footprint "R0805")
      (description "RES 5.10K OHM 1/8W 1% 0805 SMD")
      (fields
        (field (name "MANUFACTURER") "Panasonic - ECG")
        (field (name "MANUFACTURER PART NUMBER") "ERJ-6ENF5101V")
      )
      (libsource (lib "eRCL") (part "ERJ-6ENF5101V"))
    )
    (comp (ref "R84")
      (value "5.1k")
      (footprint "R0805")
      (description "RES 5.10K OHM 1/8W 1% 0805 SMD")
      (fields
        (field (name "MANUFACTURER") "Panasonic - ECG")
        (field (name "MANUFACTURER PART NUMBER") "ERJ-6ENF5101V")
      )
      (libsource (lib "eRCL") (part "ERJ-6ENF5101V"))
    )
    (comp (ref "R85")
      (value "5.1k")
      (footprint "R0805")
      (description "RES 5.10K OHM 1/8W 1% 0805 SMD")
      (fields
        (field (name "MANUFACTURER") "Panasonic - ECG")
        (field (name "MANUFACTURER PART NUMBER") "ERJ-6ENF5101V")
      )
      (libsource (lib "eRCL") (part "ERJ-6ENF5101V"))
    )
    (comp (ref "R86")
      (value "5.1k")
      (footprint "R0805")
      (description "RES 5.10K OHM 1/8W 1% 0805 SMD")
      (fields
        (field (name "MANUFACTURER") "Panasonic - ECG")
        (field (name "MANUFACTURER PART NUMBER") "ERJ-6ENF5101V")
      )
      (libsource (lib "eRCL") (part "ERJ-6ENF5101V"))
    )
    (comp (ref "R87")
      (value "5.1k")
      (footprint "R0805")
      (description "RES 5.10K OHM 1/8W 1% 0805 SMD")
      (fields
        (field (name "MANUFACTURER") "Panasonic - ECG")
        (field (name "MANUFACTURER PART NUMBER") "ERJ-6ENF5101V")
      )
      (libsource (lib "eRCL") (part "ERJ-6ENF5101V"))
    )
    (comp (ref "R88")
      (value "5.1k")
      (footprint "R0805")
      (description "RES 5.10K OHM 1/8W 1% 0805 SMD")
      (fields
        (field (name "MANUFACTURER") "Panasonic - ECG")
        (field (name "MANUFACTURER PART NUMBER") "ERJ-6ENF5101V")
      )
      (libsource (lib "eRCL") (part "ERJ-6ENF5101V"))
    )
    (comp (ref "R89")
      (value "5.1k")
      (footprint "R0805")
      (description "RES 5.10K OHM 1/8W 1% 0805 SMD")
      (fields
        (field (name "MANUFACTURER") "Panasonic - ECG")
        (field (name "MANUFACTURER PART NUMBER") "ERJ-6ENF5101V")
      )
      (libsource (lib "eRCL") (part "ERJ-6ENF5101V"))
    )
    (comp (ref "R90")
      (value "5.1k")
      (footprint "R0805")
      (description "RES 5.10K OHM 1/8W 1% 0805 SMD")
      (fields
        (field (name "MANUFACTURER") "Panasonic - ECG")
        (field (name "MANUFACTURER PART NUMBER") "ERJ-6ENF5101V")
      )
      (libsource (lib "eRCL") (part "ERJ-6ENF5101V"))
    )
    (comp (ref "R91")
      (value "5.1k")
      (footprint "R0805")
      (description "RES 5.10K OHM 1/8W 1% 0805 SMD")
      (fields
        (field (name "MANUFACTURER") "Panasonic - ECG")
        (field (name "MANUFACTURER PART NUMBER") "ERJ-6ENF5101V")
      )
      (libsource (lib "eRCL") (part "ERJ-6ENF5101V"))
    )
    (comp (ref "R92")
      (value "5.1k")
      (footprint "R0805")
      (description "RES 5.10K OHM 1/8W 1% 0805 SMD")
      (fields
        (field (name "MANUFACTURER") "Panasonic - ECG")
        (field (name "MANUFACTURER PART NUMBER") "ERJ-6ENF5101V")
      )
      (libsource (lib "eRCL") (part "ERJ-6ENF5101V"))
    )
    (comp (ref "R93")
      (value "5.1k")
      (footprint "R0805")
      (description "RES 5.10K OHM 1/8W 1% 0805 SMD")
      (fields
        (field (name "MANUFACTURER") "Panasonic - ECG")
        (field (name "MANUFACTURER PART NUMBER") "ERJ-6ENF5101V")
      )
      (libsource (lib "eRCL") (part "ERJ-6ENF5101V"))
    )
    (comp (ref "R94")
      (value "5.1k")
      (footprint "R0805")
      (description "RES 5.10K OHM 1/8W 1% 0805 SMD")
      (fields
        (field (name "MANUFACTURER") "Panasonic - ECG")
        (field (name "MANUFACTURER PART NUMBER") "ERJ-6ENF5101V")
      )
      (libsource (lib "eRCL") (part "ERJ-6ENF5101V"))
    )
    (comp (ref "R95")
      (value "5.1k")
      (footprint "R0805")
      (description "RES 5.10K OHM 1/8W 1% 0805 SMD")
      (fields
        (field (name "MANUFACTURER") "Panasonic - ECG")
        (field (name "MANUFACTURER PART NUMBER") "ERJ-6ENF5101V")
      )
      (libsource (lib "eRCL") (part "ERJ-6ENF5101V"))
    )
    (comp (ref "R96")
      (value "5.1k")
      (footprint "R0805")
      (description "RES 5.10K OHM 1/8W 1% 0805 SMD")
      (fields
        (field (name "MANUFACTURER") "Panasonic - ECG")
        (field (name "MANUFACTURER PART NUMBER") "ERJ-6ENF5101V")
      )
      (libsource (lib "eRCL") (part "ERJ-6ENF5101V"))
    )
    (comp (ref "R97")
      (value "5.1k")
      (footprint "R0805")
      (description "RES 5.10K OHM 1/8W 1% 0805 SMD")
      (fields
        (field (name "MANUFACTURER") "Panasonic - ECG")
        (field (name "MANUFACTURER PART NUMBER") "ERJ-6ENF5101V")
      )
      (libsource (lib "eRCL") (part "ERJ-6ENF5101V"))
    )
    (comp (ref "R98")
      (value "5.1k")
      (footprint "R0805")
      (description "RES 5.10K OHM 1/8W 1% 0805 SMD")
      (fields
        (field (name "MANUFACTURER") "Panasonic - ECG")
        (field (name "MANUFACTURER PART NUMBER") "ERJ-6ENF5101V")
      )
      (libsource (lib "eRCL") (part "ERJ-6ENF5101V"))
    )
    (comp (ref "R99")
      (value "5.1k")
      (footprint "R0805")
      (description "RES 5.10K OHM 1/8W 1% 0805 SMD")
      (fields
        (field (name "MANUFACTURER") "Panasonic - ECG")
        (field (name "MANUFACTURER PART NUMBER") "ERJ-6ENF5101V")
      )
      (libsource (lib "eRCL") (part "ERJ-6ENF5101V"))
    )
    (comp (ref "R100")
      (value "5.1k")
      (footprint "R0805")
      (description "RES 5.10K OHM 1/8W 1% 0805 SMD")
      (fields
        (field (name "MANUFACTURER") "Panasonic - ECG")
        (field (name "MANUFACTURER PART NUMBER") "ERJ-6ENF5101V")
      )
      (libsource (lib "eRCL") (part "ERJ-6ENF5101V"))
    )
    (comp (ref "R101")
      (value "5.1k")
      (footprint "R0805")
      (description "RES 5.10K OHM 1/8W 1% 0805 SMD")
      (fields
        (field (name "MANUFACTURER") "Panasonic - ECG")
        (field (name "MANUFACTURER PART NUMBER") "ERJ-6ENF5101V")
      )
      (libsource (lib "eRCL") (part "ERJ-6ENF5101V"))
    )
    (comp (ref "R102")
      (value "5.1k")
      (footprint "R0805")
      (description "RES 5.10K OHM 1/8W 1% 0805 SMD")
      (fields
        (field (name "MANUFACTURER") "Panasonic - ECG")
        (field (name "MANUFACTURER PART NUMBER") "ERJ-6ENF5101V")
      )
      (libsource (lib "eRCL") (part "ERJ-6ENF5101V"))
    )
    (comp (ref "R103")
      (value "5.1k")
      (footprint "R0805")
      (description "RES 5.10K OHM 1/8W 1% 0805 SMD")
      (fields
        (field (name "MANUFACTURER") "Panasonic - ECG")
        (field (name "MANUFACTURER PART NUMBER") "ERJ-6ENF5101V")
      )
      (libsource (lib "eRCL") (part "ERJ-6ENF5101V"))
    )
    (comp (ref "R104")
      (value "5.1k")
      (footprint "R0805")
      (description "RES 5.10K OHM 1/8W 1% 0805 SMD")
      (fields
        (field (name "MANUFACTURER") "Panasonic - ECG")
        (field (name "MANUFACTURER PART NUMBER") "ERJ-6ENF5101V")
      )
      (libsource (lib "eRCL") (part "ERJ-6ENF5101V"))
    )
    (comp (ref "U1")
      (value "IS/SN74HC573DWZ")
      (footprint "SOIC300-20")
      (description "Octal D-Type Transparent Latch with 3-State Outputs")
      (fields
        (field (name "MANUFACTURER") "NXP Semiconductors")
        (field (name "MANUFACTURER PART NUMBER") "74HC573D-T")
        (field (name "SOURCE") "Digikey")
      )
      (libsource (lib "ScoreBoard") (part "IS/SN74HC573DWZ"))
    )
    (comp (ref "U10")
      (value "IS/SN74HC541DWZ")
      (footprint "SOIC300-20")
      (description "Octal Buffer and Line Driver with 3-State Outputs")
      (fields
        (field (name "MANUFACTURER") "Texas Instruments")
        (field (name "MANUFACTURER PART NUMBER") "SN74HC541DWR")
        (field (name "SOURCE") "Digikey")
      )
      (libsource (lib "ScoreBoard") (part "IS/SN74HC541DWZ"))
    )
    (comp (ref "U14")
      (value "IS/SN74HC573DWZ")
      (footprint "SOIC300-20")
      (description "Octal D-Type Transparent Latch with 3-State Outputs")
      (fields
        (field (name "MANUFACTURER") "NXP Semiconductors")
        (field (name "MANUFACTURER PART NUMBER") "74HC573D-T")
        (field (name "SOURCE") "Digikey")
      )
      (libsource (lib "ScoreBoard") (part "IS/SN74HC573DWZ"))
    )
    (comp (ref "U18")
      (value "IS/SN74HC541DWZ")
      (footprint "SOIC300-20")
      (description "Octal Buffer and Line Driver with 3-State Outputs")
      (fields
        (field (name "MANUFACTURER") "Texas Instruments")
        (field (name "MANUFACTURER PART NUMBER") "SN74HC541DWR")
        (field (name "SOURCE") "Digikey")
      )
      (libsource (lib "ScoreBoard") (part "IS/SN74HC541DWZ"))
    )
  )
  (nets
    (net (code "1") (name "/CLK6") (class "Default")
      (node (ref "U1") (pin "11") (pinfunction "LE_11") (pintype "input"))
    )
    (net (code "2") (name "/CLK7") (class "Default")
      (node (ref "U14") (pin "11") (pinfunction "LE_11") (pintype "input"))
    )
    (net (code "3") (name "/D0") (class "Default")
      (node (ref "U1") (pin "2") (pinfunction "D1_2") (pintype "input"))
      (node (ref "U10") (pin "18") (pinfunction "Y1_18") (pintype "tri_state"))
      (node (ref "U14") (pin "2") (pinfunction "D1_2") (pintype "input"))
      (node (ref "U18") (pin "18") (pinfunction "Y1_18") (pintype "tri_state"))
    )
    (net (code "4") (name "/D1") (class "Default")
      (node (ref "U1") (pin "3") (pinfunction "D2_3") (pintype "input"))
      (node (ref "U10") (pin "17") (pinfunction "Y2_17") (pintype "tri_state"))
      (node (ref "U14") (pin "3") (pinfunction "D2_3") (pintype "input"))
      (node (ref "U18") (pin "17") (pinfunction "Y2_17") (pintype "tri_state"))
    )
    (net (code "5") (name "/D2") (class "Default")
      (node (ref "U1") (pin "4") (pinfunction "D3_4") (pintype "input"))
      (node (ref "U10") (pin "16") (pinfunction "Y3_16") (pintype "tri_state"))
      (node (ref "U14") (pin "4") (pinfunction "D3_4") (pintype "input"))
      (node (ref "U18") (pin "16") (pinfunction "Y3_16") (pintype "tri_state"))
    )
    (net (code "6") (name "/D3") (class "Default")
      (node (ref "U1") (pin "5") (pinfunction "D4_5") (pintype "input"))
      (node (ref "U10") (pin "15") (pinfunction "Y4_15") (pintype "tri_state"))
      (node (ref "U14") (pin "5") (pinfunction "D4_5") (pintype "input"))
      (node (ref "U18") (pin "15") (pinfunction "Y4_15") (pintype "tri_state"))
    )
    (net (code "7") (name "/D4") (class "Default")
      (node (ref "U1") (pin "6") (pinfunction "D5_6") (pintype "input"))
      (node (ref "U10") (pin "14") (pinfunction "Y5_14") (pintype "tri_state"))
      (node (ref "U14") (pin "6") (pinfunction "D5_6") (pintype "input"))
      (node (ref "U18") (pin "14") (pinfunction "Y5_14") (pintype "tri_state"))
    )
    (net (code "8") (name "/D5") (class "Default")
      (node (ref "U1") (pin "7") (pinfunction "D6_7") (pintype "input"))
      (node (ref "U10") (pin "13") (pinfunction "Y6_13") (pintype "tri_state"))
      (node (ref "U14") (pin "7") (pinfunction "D6_7") (pintype "input"))
      (node (ref "U18") (pin "13") (pinfunction "Y6_13") (pintype "tri_state"))
    )
    (net (code "9") (name "/D6") (class "Default")
      (node (ref "U1") (pin "8") (pinfunction "D7_8") (pintype "input"))
      (node (ref "U10") (pin "12") (pinfunction "Y7_12") (pintype "tri_state"))
      (node (ref "U14") (pin "8") (pinfunction "D7_8") (pintype "input"))
      (node (ref "U18") (pin "12") (pinfunction "Y7_12") (pintype "tri_state"))
    )
    (net (code "10") (name "/D7") (class "Default")
      (node (ref "U1") (pin "9") (pinfunction "D8_9") (pintype "input"))
      (node (ref "U10") (pin "11") (pinfunction "Y8_11") (pintype "tri_state"))
      (node (ref "U14") (pin "9") (pinfunction "D8_9") (pintype "input"))
      (node (ref "U18") (pin "11") (pinfunction "Y8_11") (pintype "tri_state"))
    )
    (net (code "11") (name "/LAMP0") (class "Default")
      (node (ref "R6") (pin "1") (pinfunction "1_1") (pintype "passive"))
    )
    (net (code "12") (name "/LAMP1") (class "Default")
      (node (ref "R7") (pin "1") (pinfunction "1_1") (pintype "passive"))
    )
    (net (code "13") (name "/LAMP2") (class "Default")
      (node (ref "R8") (pin "1") (pinfunction "1_1") (pintype "passive"))
    )
    (net (code "14") (name "/LAMP3") (class "Default")
      (node (ref "R9") (pin "1") (pinfunction "1_1") (pintype "passive"))
    )
    (net (code "15") (name "/LAMP4") (class "Default")
      (node (ref "R10") (pin "1") (pinfunction "1_1") (pintype "passive"))
    )
    (net (code "16") (name "/LAMP5") (class "Default")
      (node (ref "R11") (pin "1") (pinfunction "1_1") (pintype "passive"))
    )
    (net (code "17") (name "/LAMP6") (class "Default")
      (node (ref "R12") (pin "1") (pinfunction "1_1") (pintype "passive"))
      (node (ref "U1") (pin "19") (pinfunction "Q1_19") (pintype "tri_state"))
    )
    (net (code "18") (name "/LAMP7") (class "Default")
      (node (ref "R13") (pin "1") (pinfunction "1_1") (pintype "passive"))
      (node (ref "U1") (pin "18") (pinfunction "Q2_18") (pintype "tri_state"))
    )
    (net (code "19") (name "/LAMP8") (class "Default")
      (node (ref "R14") (pin "1") (pinfunction "1_1") (pintype "passive"))
      (node (ref "U1") (pin "17") (pinfunction "Q3_17") (pintype "tri_state"))
    )
    (net (code "20") (name "/LAMP9") (class "Default")
      (node (ref "R15") (pin "1") (pinfunction "1_1") (pintype "passive"))
      (node (ref "U1") (pin "16") (pinfunction "Q4_16") (pintype "tri_state"))
    )
    (net (code "21") (name "/LAMP10") (class "Default")
      (node (ref "R62") (pin "1") (pinfunction "1_1") (pintype "passive"))
      (node (ref "U1") (pin "15") (pinfunction "Q5_15") (pintype "tri_state"))
    )
    (net (code "22") (name "/LAMP11") (class "Default")
      (node (ref "R63") (pin "1") (pinfunction "1_1") (pintype "passive"))
      (node (ref "U1") (pin "14") (pinfunction "Q6_14") (pintype "tri_state"))
    )
    (net (code "23") (name "/LAMP12") (class "Default")
      (node (ref "R64") (pin "1") (pinfunction "1_1") (pintype "passive"))
      (node (ref "U1") (pin "13") (pinfunction "Q7_13") (pintype "tri_state"))
    )
    (net (code "24") (name "/LAMP13") (class "Default")
      (node (ref "R65") (pin "1") (pinfunction "1_1") (pintype "passive"))
      (node (ref "U1") (pin "12") (pinfunction "Q8_12") (pintype "tri_state"))
    )
    (net (code "25") (name "/LAMP14") (class "Default")
      (node (ref "R66") (pin "1") (pinfunction "1_1") (pintype "passive"))
      (node (ref "U14") (pin "19") (pinfunction "Q1_19") (pintype "tri_state"))
    )
    (net (code "26") (name "/LAMP15") (class "Default")
      (node (ref "R69") (pin "1") (pinfunction "1_1") (pintype "passive"))
      (node (ref "U14") (pin "18") (pinfunction "Q2_18") (pintype "tri_state"))
    )
    (net (code "27") (name "/LAMP16") (class "Default")
      (node (ref "R70") (pin "1") (pinfunction "1_1") (pintype "passive"))
      (node (ref "U14") (pin "17") (pinfunction "Q3_17") (pintype "tri_state"))
    )
    (net (code "28") (name "/LAMP17") (class "Default")
      (node (ref "R71") (pin "1") (pinfunction "1_1") (pintype "passive"))
      (node (ref "U14") (pin "16") (pinfunction "Q4_16") (pintype "tri_state"))
    )
    (net (code "29") (name "/LAMP18") (class "Default")
      (node (ref "R72") (pin "1") (pinfunction "1_1") (pintype "passive"))
      (node (ref "U14") (pin "15") (pinfunction "Q5_15") (pintype "tri_state"))
    )
    (net (code "30") (name "/LAMP19") (class "Default")
      (node (ref "R73") (pin "1") (pinfunction "1_1") (pintype "passive"))
      (node (ref "U14") (pin "14") (pinfunction "Q6_14") (pintype "tri_state"))
    )
    (net (code "31") (name "/LAMP20") (class "Default")
      (node (ref "U14") (pin "13") (pinfunction "Q7_13") (pintype "tri_state"))
    )
    (net (code "32") (name "/LED_OE") (class "Default")
      (node (ref "U1") (pin "1") (pinfunction "~{OE}_1") (pintype "input"))
      (node (ref "U14") (pin "1") (pinfunction "~{OE}_1") (pintype "input"))
    )
    (net (code "33") (name "/SWITCH0") (class "Default")
      (node (ref "D3") (pin "2") (pinfunction "K_2") (pintype "passive"))
      (node (ref "R33") (pin "1") (pinfunction "1_1") (pintype "passive"))
      (node (ref "R34") (pin "1") (pinfunction "1_1") (pintype "passive"))
      (node (ref "U10") (pin "2") (pinfunction "A1_2") (pintype "input"))
    )
    (net (code "34") (name "/SWITCH1") (class "Default")
      (node (ref "D4") (pin "2") (pinfunction "K_2") (pintype "passive"))
      (node (ref "R35") (pin "1") (pinfunction "1_1") (pintype "passive"))
      (node (ref "R36") (pin "1") (pinfunction "1_1") (pintype "passive"))
      (node (ref "U10") (pin "3") (pinfunction "A2_3") (pintype "input"))
    )
    (net (code "35") (name "/SWITCH2") (class "Default")
      (node (ref "D5") (pin "2") (pinfunction "K_2") (pintype "passive"))
      (node (ref "R37") (pin "1") (pinfunction "1_1") (pintype "passive"))
      (node (ref "R38") (pin "1") (pinfunction "1_1") (pintype "passive"))
      (node (ref "U10") (pin "4") (pinfunction "A3_4") (pintype "input"))
    )
    (net (code "36") (name "/SWITCH3") (class "Default")
      (node (ref "D25") (pin "2") (pinfunction "K_2") (pintype "passive"))
      (node (ref "R39") (pin "1") (pinfunction "1_1") (pintype "passive"))
      (node (ref "R40") (pin "1") (pinfunction "1_1") (pintype "passive"))
      (node (ref "U10") (pin "5") (pinfunction "A4_5") (pintype "input"))
    )
    (net (code "37") (name "/SWITCH4") (class "Default")
      (node (ref "D8") (pin "2") (pinfunction "K_2") (pintype "passive"))
      (node (ref "R41") (pin "1") (pinfunction "1_1") (pintype "passive"))
      (node (ref "R42") (pin "1") (pinfunction "1_1") (pintype "passive"))
      (node (ref "U10") (pin "6") (pinfunction "A5_6") (pintype "input"))
    )
    (net (code "38") (name "/SWITCH5") (class "Default")
      (node (ref "D9") (pin "2") (pinfunction "K_2") (pintype "passive"))
      (node (ref "R43") (pin "1") (pinfunction "1_1") (pintype "passive"))
      (node (ref "R44") (pin "1") (pinfunction "1_1") (pintype "passive"))
      (node (ref "U10") (pin "7") (pinfunction "A6_7") (pintype "input"))
    )
    (net (code "39") (name "/SWITCH6") (class "Default")
      (node (ref "D10") (pin "2") (pinfunction "K_2") (pintype "passive"))
      (node (ref "R45") (pin "1") (pinfunction "1_1") (pintype "passive"))
      (node (ref "R46") (pin "1") (pinfunction "1_1") (pintype "passive"))
      (node (ref "U10") (pin "8") (pinfunction "A7_8") (pintype "input"))
    )
    (net (code "40") (name "/SWITCH7") (class "Default")
      (node (ref "D11") (pin "2") (pinfunction "K_2") (pintype "passive"))
      (node (ref "R47") (pin "1") (pinfunction "1_1") (pintype "passive"))
      (node (ref "R48") (pin "1") (pinfunction "1_1") (pintype "passive"))
      (node (ref "U10") (pin "9") (pinfunction "A8_9") (pintype "input"))
    )
    (net (code "41") (name "/SWITCH8") (class "Default")
      (node (ref "D6") (pin "2") (pinfunction "K_2") (pintype "passive"))
      (node (ref "R49") (pin "1") (pinfunction "1_1") (pintype "passive"))
      (node (ref "R50") (pin "1") (pinfunction "1_1") (pintype "passive"))
      (node (ref "U18") (pin "2") (pinfunction "A1_2") (pintype "input"))
    )
    (net (code "42") (name "/SWITCH9") (class "Default")
      (node (ref "D7") (pin "2") (pinfunction "K_2") (pintype "passive"))
      (node (ref "R51") (pin "1") (pinfunction "1_1") (pintype "passive"))
      (node (ref "R52") (pin "1") (pinfunction "1_1") (pintype "passive"))
      (node (ref "U18") (pin "3") (pinfunction "A2_3") (pintype "input"))
    )
    (net (code "43") (name "/SWITCH10") (class "Default")
      (node (ref "D15") (pin "2") (pinfunction "K_2") (pintype "passive"))
      (node (ref "R84") (pin "1") (pinfunction "1_1") (pintype "passive"))
      (node (ref "R85") (pin "1") (pinfunction "1_1") (pintype "passive"))
      (node (ref "U18") (pin "4") (pinfunction "A3_4") (pintype "input"))
    )
    (net (code "44") (name "/SWITCH11") (class "Default")
      (node (ref "D16") (pin "2") (pinfunction "K_2") (pintype "passive"))
      (node (ref "R86") (pin "1") (pinfunction "1_1") (pintype "passive"))
      (node (ref "R87") (pin "1") (pinfunction "1_1") (pintype "passive"))
      (node (ref "U18") (pin "5") (pinfunction "A4_5") (pintype "input"))
    )
    (net (code "45") (name "/SWITCH12") (class "Default")
      (node (ref "D17") (pin "2") (pinfunction "K_2") (pintype "passive"))
      (node (ref "R88") (pin "1") (pinfunction "1_1") (pintype "passive"))
      (node (ref "R89") (pin "1") (pinfunction "1_1") (pintype "passive"))
      (node (ref "U18") (pin "6") (pinfunction "A5_6") (pintype "input"))
    )
    (net (code "46") (name "/SWITCH13") (class "Default")
      (node (ref "D18") (pin "2") (pinfunction "K_2") (pintype "passive"))
      (node (ref "R90") (pin "1") (pinfunction "1_1") (pintype "passive"))
      (node (ref "R91") (pin "1") (pinfunction "1_1") (pintype "passive"))
      (node (ref "U18") (pin "7") (pinfunction "A6_7") (pintype "input"))
    )
    (net (code "47") (name "/SWITCH14") (class "Default")
      (node (ref "D19") (pin "2") (pinfunction "K_2") (pintype "passive"))
      (node (ref "R92") (pin "1") (pinfunction "1_1") (pintype "passive"))
      (node (ref "R93") (pin "1") (pinfunction "1_1") (pintype "passive"))
      (node (ref "U18") (pin "8") (pinfunction "A7_8") (pintype "input"))
    )
    (net (code "48") (name "/SWITCH15") (class "Default")
      (node (ref "D20") (pin "2") (pinfunction "K_2") (pintype "passive"))
      (node (ref "R94") (pin "1") (pinfunction "1_1") (pintype "passive"))
      (node (ref "R95") (pin "1") (pinfunction "1_1") (pintype "passive"))
      (node (ref "U18") (pin "9") (pinfunction "A8_9") (pintype "input"))
    )
    (net (code "49") (name "/SWITCH16") (class "Default")
      (node (ref "D21") (pin "2") (pinfunction "K_2") (pintype "passive"))
      (node (ref "R96") (pin "1") (pinfunction "1_1") (pintype "passive"))
      (node (ref "R97") (pin "1") (pinfunction "1_1") (pintype "passive"))
    )
    (net (code "50") (name "/SWITCH17") (class "Default")
      (node (ref "D22") (pin "2") (pinfunction "K_2") (pintype "passive"))
      (node (ref "R98") (pin "1") (pinfunction "1_1") (pintype "passive"))
      (node (ref "R99") (pin "1") (pinfunction "1_1") (pintype "passive"))
    )
    (net (code "51") (name "/SWITCH18") (class "Default")
      (node (ref "D23") (pin "2") (pinfunction "K_2") (pintype "passive"))
      (node (ref "R100") (pin "1") (pinfunction "1_1") (pintype "passive"))
      (node (ref "R101") (pin "1") (pinfunction "1_1") (pintype "passive"))
    )
    (net (code "52") (name "/SWITCH19") (class "Default")
      (node (ref "D24") (pin "2") (pinfunction "K_2") (pintype "passive"))
      (node (ref "R102") (pin "1") (pinfunction "1_1") (pintype "passive"))
      (node (ref "R103") (pin "1") (pinfunction "1_1") (pintype "passive"))
    )
    (net (code "53") (name "/SWITCHES0-7") (class "Default")
      (node (ref "R55") (pin "2") (pinfunction "2_2") (pintype "passive"))
      (node (ref "U10") (pin "1") (pinfunction "~{OE}1_1") (pintype "input"))
      (node (ref "U10") (pin "19") (pinfunction "~{OE}2_19") (pintype "input"))
    )
    (net (code "54") (name "/SWITCHES8-15") (class "Default")
      (node (ref "R104") (pin "2") (pinfunction "2_2") (pintype "passive"))
      (node (ref "U18") (pin "1") (pinfunction "~{OE}1_1") (pintype "input"))
      (node (ref "U18") (pin "19") (pinfunction "~{OE}2_19") (pintype "input"))
    )
    (net (code "55") (name "GND") (class "Default")
      (node (ref "C30") (pin "2") (pinfunction "2_2") (pintype "passive"))
      (node (ref "C37") (pin "2") (pinfunction "2_2") (pintype "passive"))
      (node (ref "C4") (pin "2") (pinfunction "2_2") (pintype "passive"))
      (node (ref "C46") (pin "2") (pinfunction "2_2") (pintype "passive"))
      (node (ref "D10") (pin "1") (pinfunction "A_1") (pintype "passive"))
      (node (ref "D11") (pin "1") (pinfunction "A_1") (pintype "passive"))
      (node (ref "D15") (pin "1") (pinfunction "A_1") (pintype "passive"))
      (node (ref "D16") (pin "1") (pinfunction "A_1") (pintype "passive"))
      (node (ref "D17") (pin "1") (pinfunction "A_1") (pintype "passive"))
      (node (ref "D18") (pin "1") (pinfunction "A_1") (pintype "passive"))
      (node (ref "D19") (pin "1") (pinfunction "A_1") (pintype "passive"))
      (node (ref "D20") (pin "1") (pinfunction "A_1") (pintype "passive"))
      (node (ref "D21") (pin "1") (pinfunction "A_1") (pintype "passive"))
      (node (ref "D22") (pin "1") (pinfunction "A_1") (pintype "passive"))
      (node (ref "D23") (pin "1") (pinfunction "A_1") (pintype "passive"))
      (node (ref "D24") (pin "1") (pinfunction "A_1") (pintype "passive"))
      (node (ref "D25") (pin "1") (pinfunction "A_1") (pintype "passive"))
      (node (ref "D3") (pin "1") (pinfunction "A_1") (pintype "passive"))
      (node (ref "D4") (pin "1") (pinfunction "A_1") (pintype "passive"))
      (node (ref "D5") (pin "1") (pinfunction "A_1") (pintype "passive"))
      (node (ref "D6") (pin "1") (pinfunction "A_1") (pintype "passive"))
      (node (ref "D7") (pin "1") (pinfunction "A_1") (pintype "passive"))
      (node (ref "D8") (pin "1") (pinfunction "A_1") (pintype "passive"))
      (node (ref "D9") (pin "1") (pinfunction "A_1") (pintype "passive"))
      (node (ref "Q1") (pin "3") (pinfunction "S_3") (pintype "passive"))
      (node (ref "Q10") (pin "3") (pinfunction "S_3") (pintype "passive"))
      (node (ref "Q11") (pin "3") (pinfunction "S_3") (pintype "passive"))
      (node (ref "Q12") (pin "3") (pinfunction "S_3") (pintype "passive"))
      (node (ref "Q13") (pin "3") (pinfunction "S_3") (pintype "passive"))
      (node (ref "Q14") (pin "3") (pinfunction "S_3") (pintype "passive"))
      (node (ref "Q15") (pin "3") (pinfunction "S_3") (pintype "passive"))
      (node (ref "Q16") (pin "3") (pinfunction "S_3") (pintype "passive"))
      (node (ref "Q17") (pin "3") (pinfunction "S_3") (pintype "passive"))
      (node (ref "Q18") (pin "3") (pinfunction "S_3") (pintype "passive"))
      (node (ref "Q19") (pin "3") (pinfunction "S_3") (pintype "passive"))
      (node (ref "Q2") (pin "3") (pinfunction "S_3") (pintype "passive"))
      (node (ref "Q20") (pin "3") (pinfunction "S_3") (pintype "passive"))
      (node (ref "Q3") (pin "3") (pinfunction "S_3") (pintype "passive"))
      (node (ref "Q4") (pin "3") (pinfunction "S_3") (pintype "passive"))
      (node (ref "Q5") (pin "3") (pinfunction "S_3") (pintype "passive"))
      (node (ref "Q6") (pin "3") (pinfunction "S_3") (pintype "passive"))
      (node (ref "Q7") (pin "3") (pinfunction "S_3") (pintype "passive"))
      (node (ref "Q8") (pin "3") (pinfunction "S_3") (pintype "passive"))
      (node (ref "Q9") (pin "3") (pinfunction "S_3") (pintype "passive"))
      (node (ref "R101") (pin "2") (pinfunction "2_2") (pintype "passive"))
      (node (ref "R103") (pin "2") (pinfunction "2_2") (pintype "passive"))
      (node (ref "R34") (pin "2") (pinfunction "2_2") (pintype "passive"))
      (node (ref "R36") (pin "2") (pinfunction "2_2") (pintype "passive"))
      (node (ref "R38") (pin "2") (pinfunction "2_2") (pintype "passive"))
      (node (ref "R40") (pin "2") (pinfunction "2_2") (pintype "passive"))
      (node (ref "R42") (pin "2") (pinfunction "2_2") (pintype "passive"))
      (node (ref "R44") (pin "2") (pinfunction "2_2") (pintype "passive"))
      (node (ref "R46") (pin "2") (pinfunction "2_2") (pintype "passive"))
      (node (ref "R48") (pin "2") (pinfunction "2_2") (pintype "passive"))
      (node (ref "R50") (pin "2") (pinfunction "2_2") (pintype "passive"))
      (node (ref "R52") (pin "2") (pinfunction "2_2") (pintype "passive"))
      (node (ref "R85") (pin "2") (pinfunction "2_2") (pintype "passive"))
      (node (ref "R87") (pin "2") (pinfunction "2_2") (pintype "passive"))
      (node (ref "R89") (pin "2") (pinfunction "2_2") (pintype "passive"))
      (node (ref "R91") (pin "2") (pinfunction "2_2") (pintype "passive"))
      (node (ref "R93") (pin "2") (pinfunction "2_2") (pintype "passive"))
      (node (ref "R95") (pin "2") (pinfunction "2_2") (pintype "passive"))
      (node (ref "R97") (pin "2") (pinfunction "2_2") (pintype "passive"))
      (node (ref "R99") (pin "2") (pinfunction "2_2") (pintype "passive"))
      (node (ref "U1") (pin "10") (pinfunction "GND_10") (pintype "power_in"))
      (node (ref "U10") (pin "10") (pinfunction "GND_10") (pintype "power_in"))
      (node (ref "U14") (pin "10") (pinfunction "GND_10") (pintype "power_in"))
      (node (ref "U18") (pin "10") (pinfunction "GND_10") (pintype "power_in"))
    )
    (net (code "56") (name "Net-(J11-Pad1)") (class "Default")
      (node (ref "J11") (pin "1") (pinfunction "1_1") (pintype "passive"))
      (node (ref "R33") (pin "2") (pinfunction "2_2") (pintype "passive"))
    )
    (net (code "57") (name "Net-(J11-Pad2)") (class "Default")
      (node (ref "J11") (pin "2") (pinfunction "2_2") (pintype "passive"))
      (node (ref "R35") (pin "2") (pinfunction "2_2") (pintype "passive"))
    )
    (net (code "58") (name "Net-(J11-Pad3)") (class "Default")
      (node (ref "J11") (pin "3") (pinfunction "3_3") (pintype "passive"))
      (node (ref "R37") (pin "2") (pinfunction "2_2") (pintype "passive"))
    )
    (net (code "59") (name "Net-(J11-Pad4)") (class "Default")
      (node (ref "J11") (pin "4") (pinfunction "4_4") (pintype "passive"))
      (node (ref "R39") (pin "2") (pinfunction "2_2") (pintype "passive"))
    )
    (net (code "60") (name "Net-(J11-Pad5)") (class "Default")
      (node (ref "J11") (pin "5") (pinfunction "5_5") (pintype "passive"))
      (node (ref "R41") (pin "2") (pinfunction "2_2") (pintype "passive"))
    )
    (net (code "61") (name "Net-(J12-Pad1)") (class "Default")
      (node (ref "J12") (pin "1") (pinfunction "1_1") (pintype "passive"))
      (node (ref "R43") (pin "2") (pinfunction "2_2") (pintype "passive"))
    )
    (net (code "62") (name "Net-(J12-Pad2)") (class "Default")
      (node (ref "J12") (pin "2") (pinfunction "2_2") (pintype "passive"))
      (node (ref "R45") (pin "2") (pinfunction "2_2") (pintype "passive"))
    )
    (net (code "63") (name "Net-(J12-Pad3)") (class "Default")
      (node (ref "J12") (pin "3") (pinfunction "3_3") (pintype "passive"))
      (node (ref "R47") (pin "2") (pinfunction "2_2") (pintype "passive"))
    )
    (net (code "64") (name "Net-(J12-Pad4)") (class "Default")
      (node (ref "J12") (pin "4") (pinfunction "4_4") (pintype "passive"))
      (node (ref "R49") (pin "2") (pinfunction "2_2") (pintype "passive"))
    )
    (net (code "65") (name "Net-(J12-Pad5)") (class "Default")
      (node (ref "J12") (pin "5") (pinfunction "5_5") (pintype "passive"))
      (node (ref "R51") (pin "2") (pinfunction "2_2") (pintype "passive"))
    )
    (net (code "66") (name "Net-(J16-Pad1)") (class "Default")
      (node (ref "J16") (pin "1") (pinfunction "1_1") (pintype "passive"))
      (node (ref "R84") (pin "2") (pinfunction "2_2") (pintype "passive"))
    )
    (net (code "67") (name "Net-(J16-Pad2)") (class "Default")
      (node (ref "J16") (pin "2") (pinfunction "2_2") (pintype "passive"))
      (node (ref "R86") (pin "2") (pinfunction "2_2") (pintype "passive"))
    )
    (net (code "68") (name "Net-(J16-Pad3)") (class "Default")
      (node (ref "J16") (pin "3") (pinfunction "3_3") (pintype "passive"))
      (node (ref "R88") (pin "2") (pinfunction "2_2") (pintype "passive"))
    )
    (net (code "69") (name "Net-(J16-Pad4)") (class "Default")
      (node (ref "J16") (pin "4") (pinfunction "4_4") (pintype "passive"))
      (node (ref "R90") (pin "2") (pinfunction "2_2") (pintype "passive"))
    )
    (net (code "70") (name "Net-(J16-Pad5)") (class "Default")
      (node (ref "J16") (pin "5") (pinfunction "5_5") (pintype "passive"))
      (node (ref "R92") (pin "2") (pinfunction "2_2") (pintype "passive"))
    )
    (net (code "71") (name "Net-(J17-Pad1)") (class "Default")
      (node (ref "J17") (pin "1") (pinfunction "1_1") (pintype "passive"))
      (node (ref "R94") (pin "2") (pinfunction "2_2") (pintype "passive"))
    )
    (net (code "72") (name "Net-(J17-Pad2)") (class "Default")
      (node (ref "J17") (pin "2") (pinfunction "2_2") (pintype "passive"))
      (node (ref "R96") (pin "2") (pinfunction "2_2") (pintype "passive"))
    )
    (net (code "73") (name "Net-(J17-Pad3)") (class "Default")
      (node (ref "J17") (pin "3") (pinfunction "3_3") (pintype "passive"))
      (node (ref "R98") (pin "2") (pinfunction "2_2") (pintype "passive"))
    )
    (net (code "74") (name "Net-(J17-Pad4)") (class "Default")
      (node (ref "J17") (pin "4") (pinfunction "4_4") (pintype "passive"))
      (node (ref "R100") (pin "2") (pinfunction "2_2") (pintype "passive"))
    )
    (net (code "75") (name "Net-(J17-Pad5)") (class "Default")
      (node (ref "J17") (pin "5") (pinfunction "5_5") (pintype "passive"))
      (node (ref "R102") (pin "2") (pinfunction "2_2") (pintype "passive"))
    )
    (net (code "76") (name "Net-(Q1-D)") (class "Default")
      (node (ref "J11") (pin "12") (pinfunction "12_12") (pintype "passive"))
      (node (ref "Q1") (pin "2") (pinfunction "D_2") (pintype "passive"))
    )
    (net (code "77") (name "Net-(Q1-G)") (class "Default")
      (node (ref "Q1") (pin "1") (pinfunction "G_1") (pintype "passive"))
      (node (ref "R6") (pin "2") (pinfunction "2_2") (pintype "passive"))
    )
    (net (code "78") (name "Net-(Q2-D)") (class "Default")
      (node (ref "J11") (pin "11") (pinfunction "11_11") (pintype "passive"))
      (node (ref "Q2") (pin "2") (pinfunction "D_2") (pintype "passive"))
    )
    (net (code "79") (name "Net-(Q2-G)") (class "Default")
      (node (ref "Q2") (pin "1") (pinfunction "G_1") (pintype "passive"))
      (node (ref "R7") (pin "2") (pinfunction "2_2") (pintype "passive"))
    )
    (net (code "80") (name "Net-(Q3-D)") (class "Default")
      (node (ref "J11") (pin "10") (pinfunction "10_10") (pintype "passive"))
      (node (ref "Q3") (pin "2") (pinfunction "D_2") (pintype "passive"))
    )
    (net (code "81") (name "Net-(Q3-G)") (class "Default")
      (node (ref "Q3") (pin "1") (pinfunction "G_1") (pintype "passive"))
      (node (ref "R8") (pin "2") (pinfunction "2_2") (pintype "passive"))
    )
    (net (code "82") (name "Net-(Q4-D)") (class "Default")
      (node (ref "J11") (pin "9") (pinfunction "9_9") (pintype "passive"))
      (node (ref "Q4") (pin "2") (pinfunction "D_2") (pintype "passive"))
    )
    (net (code "83") (name "Net-(Q4-G)") (class "Default")
      (node (ref "Q4") (pin "1") (pinfunction "G_1") (pintype "passive"))
      (node (ref "R9") (pin "2") (pinfunction "2_2") (pintype "passive"))
    )
    (net (code "84") (name "Net-(Q5-D)") (class "Default")
      (node (ref "J11") (pin "8") (pinfunction "8_8") (pintype "passive"))
      (node (ref "Q5") (pin "2") (pinfunction "D_2") (pintype "passive"))
    )
    (net (code "85") (name "Net-(Q5-G)") (class "Default")
      (node (ref "Q5") (pin "1") (pinfunction "G_1") (pintype "passive"))
      (node (ref "R10") (pin "2") (pinfunction "2_2") (pintype "passive"))
    )
    (net (code "86") (name "Net-(Q6-D)") (class "Default")
      (node (ref "J12") (pin "12") (pinfunction "12_12") (pintype "passive"))
      (node (ref "Q6") (pin "2") (pinfunction "D_2") (pintype "passive"))
    )
    (net (code "87") (name "Net-(Q6-G)") (class "Default")
      (node (ref "Q6") (pin "1") (pinfunction "G_1") (pintype "passive"))
      (node (ref "R11") (pin "2") (pinfunction "2_2") (pintype "passive"))
    )
    (net (code "88") (name "Net-(Q7-D)") (class "Default")
      (node (ref "J12") (pin "11") (pinfunction "11_11") (pintype "passive"))
      (node (ref "Q7") (pin "2") (pinfunction "D_2") (pintype "passive"))
    )
    (net (code "89") (name "Net-(Q7-G)") (class "Default")
      (node (ref "Q7") (pin "1") (pinfunction "G_1") (pintype "passive"))
      (node (ref "R12") (pin "2") (pinfunction "2_2") (pintype "passive"))
    )
    (net (code "90") (name "Net-(Q8-D)") (class "Default")
      (node (ref "J12") (pin "10") (pinfunction "10_10") (pintype "passive"))
      (node (ref "Q8") (pin "2") (pinfunction "D_2") (pintype "passive"))
    )
    (net (code "91") (name "Net-(Q8-G)") (class "Default")
      (node (ref "Q8") (pin "1") (pinfunction "G_1") (pintype "passive"))
      (node (ref "R13") (pin "2") (pinfunction "2_2") (pintype "passive"))
    )
    (net (code "92") (name "Net-(Q9-D)") (class "Default")
      (node (ref "J12") (pin "9") (pinfunction "9_9") (pintype "passive"))
      (node (ref "Q9") (pin "2") (pinfunction "D_2") (pintype "passive"))
    )
    (net (code "93") (name "Net-(Q9-G)") (class "Default")
      (node (ref "Q9") (pin "1") (pinfunction "G_1") (pintype "passive"))
      (node (ref "R14") (pin "2") (pinfunction "2_2") (pintype "passive"))
    )
    (net (code "94") (name "Net-(Q10-D)") (class "Default")
      (node (ref "J12") (pin "8") (pinfunction "8_8") (pintype "passive"))
      (node (ref "Q10") (pin "2") (pinfunction "D_2") (pintype "passive"))
    )
    (net (code "95") (name "Net-(Q10-G)") (class "Default")
      (node (ref "Q10") (pin "1") (pinfunction "G_1") (pintype "passive"))
      (node (ref "R15") (pin "2") (pinfunction "2_2") (pintype "passive"))
    )
    (net (code "96") (name "Net-(Q11-D)") (class "Default")
      (node (ref "J16") (pin "12") (pinfunction "12_12") (pintype "passive"))
      (node (ref "Q11") (pin "2") (pinfunction "D_2") (pintype "passive"))
    )
    (net (code "97") (name "Net-(Q11-G)") (class "Default")
      (node (ref "Q11") (pin "1") (pinfunction "G_1") (pintype "passive"))
      (node (ref "R62") (pin "2") (pinfunction "2_2") (pintype "passive"))
    )
    (net (code "98") (name "Net-(Q12-D)") (class "Default")
      (node (ref "J16") (pin "11") (pinfunction "11_11") (pintype "passive"))
      (node (ref "Q12") (pin "2") (pinfunction "D_2") (pintype "passive"))
    )
    (net (code "99") (name "Net-(Q12-G)") (class "Default")
      (node (ref "Q12") (pin "1") (pinfunction "G_1") (pintype "passive"))
      (node (ref "R63") (pin "2") (pinfunction "2_2") (pintype "passive"))
    )
    (net (code "100") (name "Net-(Q13-D)") (class "Default")
      (node (ref "J16") (pin "10") (pinfunction "10_10") (pintype "passive"))
      (node (ref "Q13") (pin "2") (pinfunction "D_2") (pintype "passive"))
    )
    (net (code "101") (name "Net-(Q13-G)") (class "Default")
      (node (ref "Q13") (pin "1") (pinfunction "G_1") (pintype "passive"))
      (node (ref "R64") (pin "2") (pinfunction "2_2") (pintype "passive"))
    )
    (net (code "102") (name "Net-(Q14-D)") (class "Default")
      (node (ref "J16") (pin "9") (pinfunction "9_9") (pintype "passive"))
      (node (ref "Q14") (pin "2") (pinfunction "D_2") (pintype "passive"))
    )
    (net (code "103") (name "Net-(Q14-G)") (class "Default")
      (node (ref "Q14") (pin "1") (pinfunction "G_1") (pintype "passive"))
      (node (ref "R65") (pin "2") (pinfunction "2_2") (pintype "passive"))
    )
    (net (code "104") (name "Net-(Q15-D)") (class "Default")
      (node (ref "J16") (pin "8") (pinfunction "8_8") (pintype "passive"))
      (node (ref "Q15") (pin "2") (pinfunction "D_2") (pintype "passive"))
    )
    (net (code "105") (name "Net-(Q15-G)") (class "Default")
      (node (ref "Q15") (pin "1") (pinfunction "G_1") (pintype "passive"))
      (node (ref "R66") (pin "2") (pinfunction "2_2") (pintype "passive"))
    )
    (net (code "106") (name "Net-(Q16-D)") (class "Default")
      (node (ref "J17") (pin "12") (pinfunction "12_12") (pintype "passive"))
      (node (ref "Q16") (pin "2") (pinfunction "D_2") (pintype "passive"))
    )
    (net (code "107") (name "Net-(Q16-G)") (class "Default")
      (node (ref "Q16") (pin "1") (pinfunction "G_1") (pintype "passive"))
      (node (ref "R69") (pin "2") (pinfunction "2_2") (pintype "passive"))
    )
    (net (code "108") (name "Net-(Q17-D)") (class "Default")
      (node (ref "J17") (pin "11") (pinfunction "11_11") (pintype "passive"))
      (node (ref "Q17") (pin "2") (pinfunction "D_2") (pintype "passive"))
    )
    (net (code "109") (name "Net-(Q17-G)") (class "Default")
      (node (ref "Q17") (pin "1") (pinfunction "G_1") (pintype "passive"))
      (node (ref "R70") (pin "2") (pinfunction "2_2") (pintype "passive"))
    )
    (net (code "110") (name "Net-(Q18-D)") (class "Default")
      (node (ref "J17") (pin "10") (pinfunction "10_10") (pintype "passive"))
      (node (ref "Q18") (pin "2") (pinfunction "D_2") (pintype "passive"))
    )
    (net (code "111") (name "Net-(Q18-G)") (class "Default")
      (node (ref "Q18") (pin "1") (pinfunction "G_1") (pintype "passive"))
      (node (ref "R71") (pin "2") (pinfunction "2_2") (pintype "passive"))
    )
    (net (code "112") (name "Net-(Q19-D)") (class "Default")
      (node (ref "J17") (pin "9") (pinfunction "9_9") (pintype "passive"))
      (node (ref "Q19") (pin "2") (pinfunction "D_2") (pintype "passive"))
    )
    (net (code "113") (name "Net-(Q19-G)") (class "Default")
      (node (ref "Q19") (pin "1") (pinfunction "G_1") (pintype "passive"))
      (node (ref "R72") (pin "2") (pinfunction "2_2") (pintype "passive"))
    )
    (net (code "114") (name "Net-(Q20-D)") (class "Default")
      (node (ref "J17") (pin "8") (pinfunction "8_8") (pintype "passive"))
      (node (ref "Q20") (pin "2") (pinfunction "D_2") (pintype "passive"))
    )
    (net (code "115") (name "Net-(Q20-G)") (class "Default")
      (node (ref "Q20") (pin "1") (pinfunction "G_1") (pintype "passive"))
      (node (ref "R73") (pin "2") (pinfunction "2_2") (pintype "passive"))
    )
    (net (code "116") (name "VCC") (class "Default")
      (node (ref "C30") (pin "1") (pinfunction "1_1") (pintype "passive"))
      (node (ref "C37") (pin "1") (pinfunction "1_1") (pintype "passive"))
      (node (ref "C4") (pin "1") (pinfunction "1_1") (pintype "passive"))
      (node (ref "C46") (pin "1") (pinfunction "1_1") (pintype "passive"))
      (node (ref "R104") (pin "1") (pinfunction "1_1") (pintype "passive"))
      (node (ref "R55") (pin "1") (pinfunction "1_1") (pintype "passive"))
      (node (ref "U1") (pin "20") (pinfunction "VCC_20") (pintype "power_in"))
      (node (ref "U10") (pin "20") (pinfunction "VCC_20") (pintype "power_in"))
      (node (ref "U14") (pin "20") (pinfunction "VCC_20") (pintype "power_in"))
      (node (ref "U18") (pin "20") (pinfunction "VCC_20") (pintype "power_in"))
    )
    (net (code "117") (name "Vbat") (class "Default")
      (node (ref "J11") (pin "6") (pinfunction "6_6") (pintype "passive"))
      (node (ref "J11") (pin "7") (pinfunction "7_7") (pintype "passive"))
      (node (ref "J12") (pin "6") (pinfunction "6_6") (pintype "passive"))
      (node (ref "J12") (pin "7") (pinfunction "7_7") (pintype "passive"))
      (node (ref "J16") (pin "6") (pinfunction "6_6") (pintype "passive"))
      (node (ref "J16") (pin "7") (pinfunction "7_7") (pintype "passive"))
      (node (ref "J17") (pin "6") (pinfunction "6_6") (pintype "passive"))
      (node (ref "J17") (pin "7") (pinfunction "7_7") (pintype "passive"))
    )
    (net (code "118") (name "unconnected-(U14-Q8-Pad12)") (class "Default")
      (node (ref "U14") (pin "12") (pinfunction "Q8_12") (pintype "tri_state"))
    )
  )
)
